# 16316339.net
KiCad netlist of a schematic drawn in EasyEDA Pro
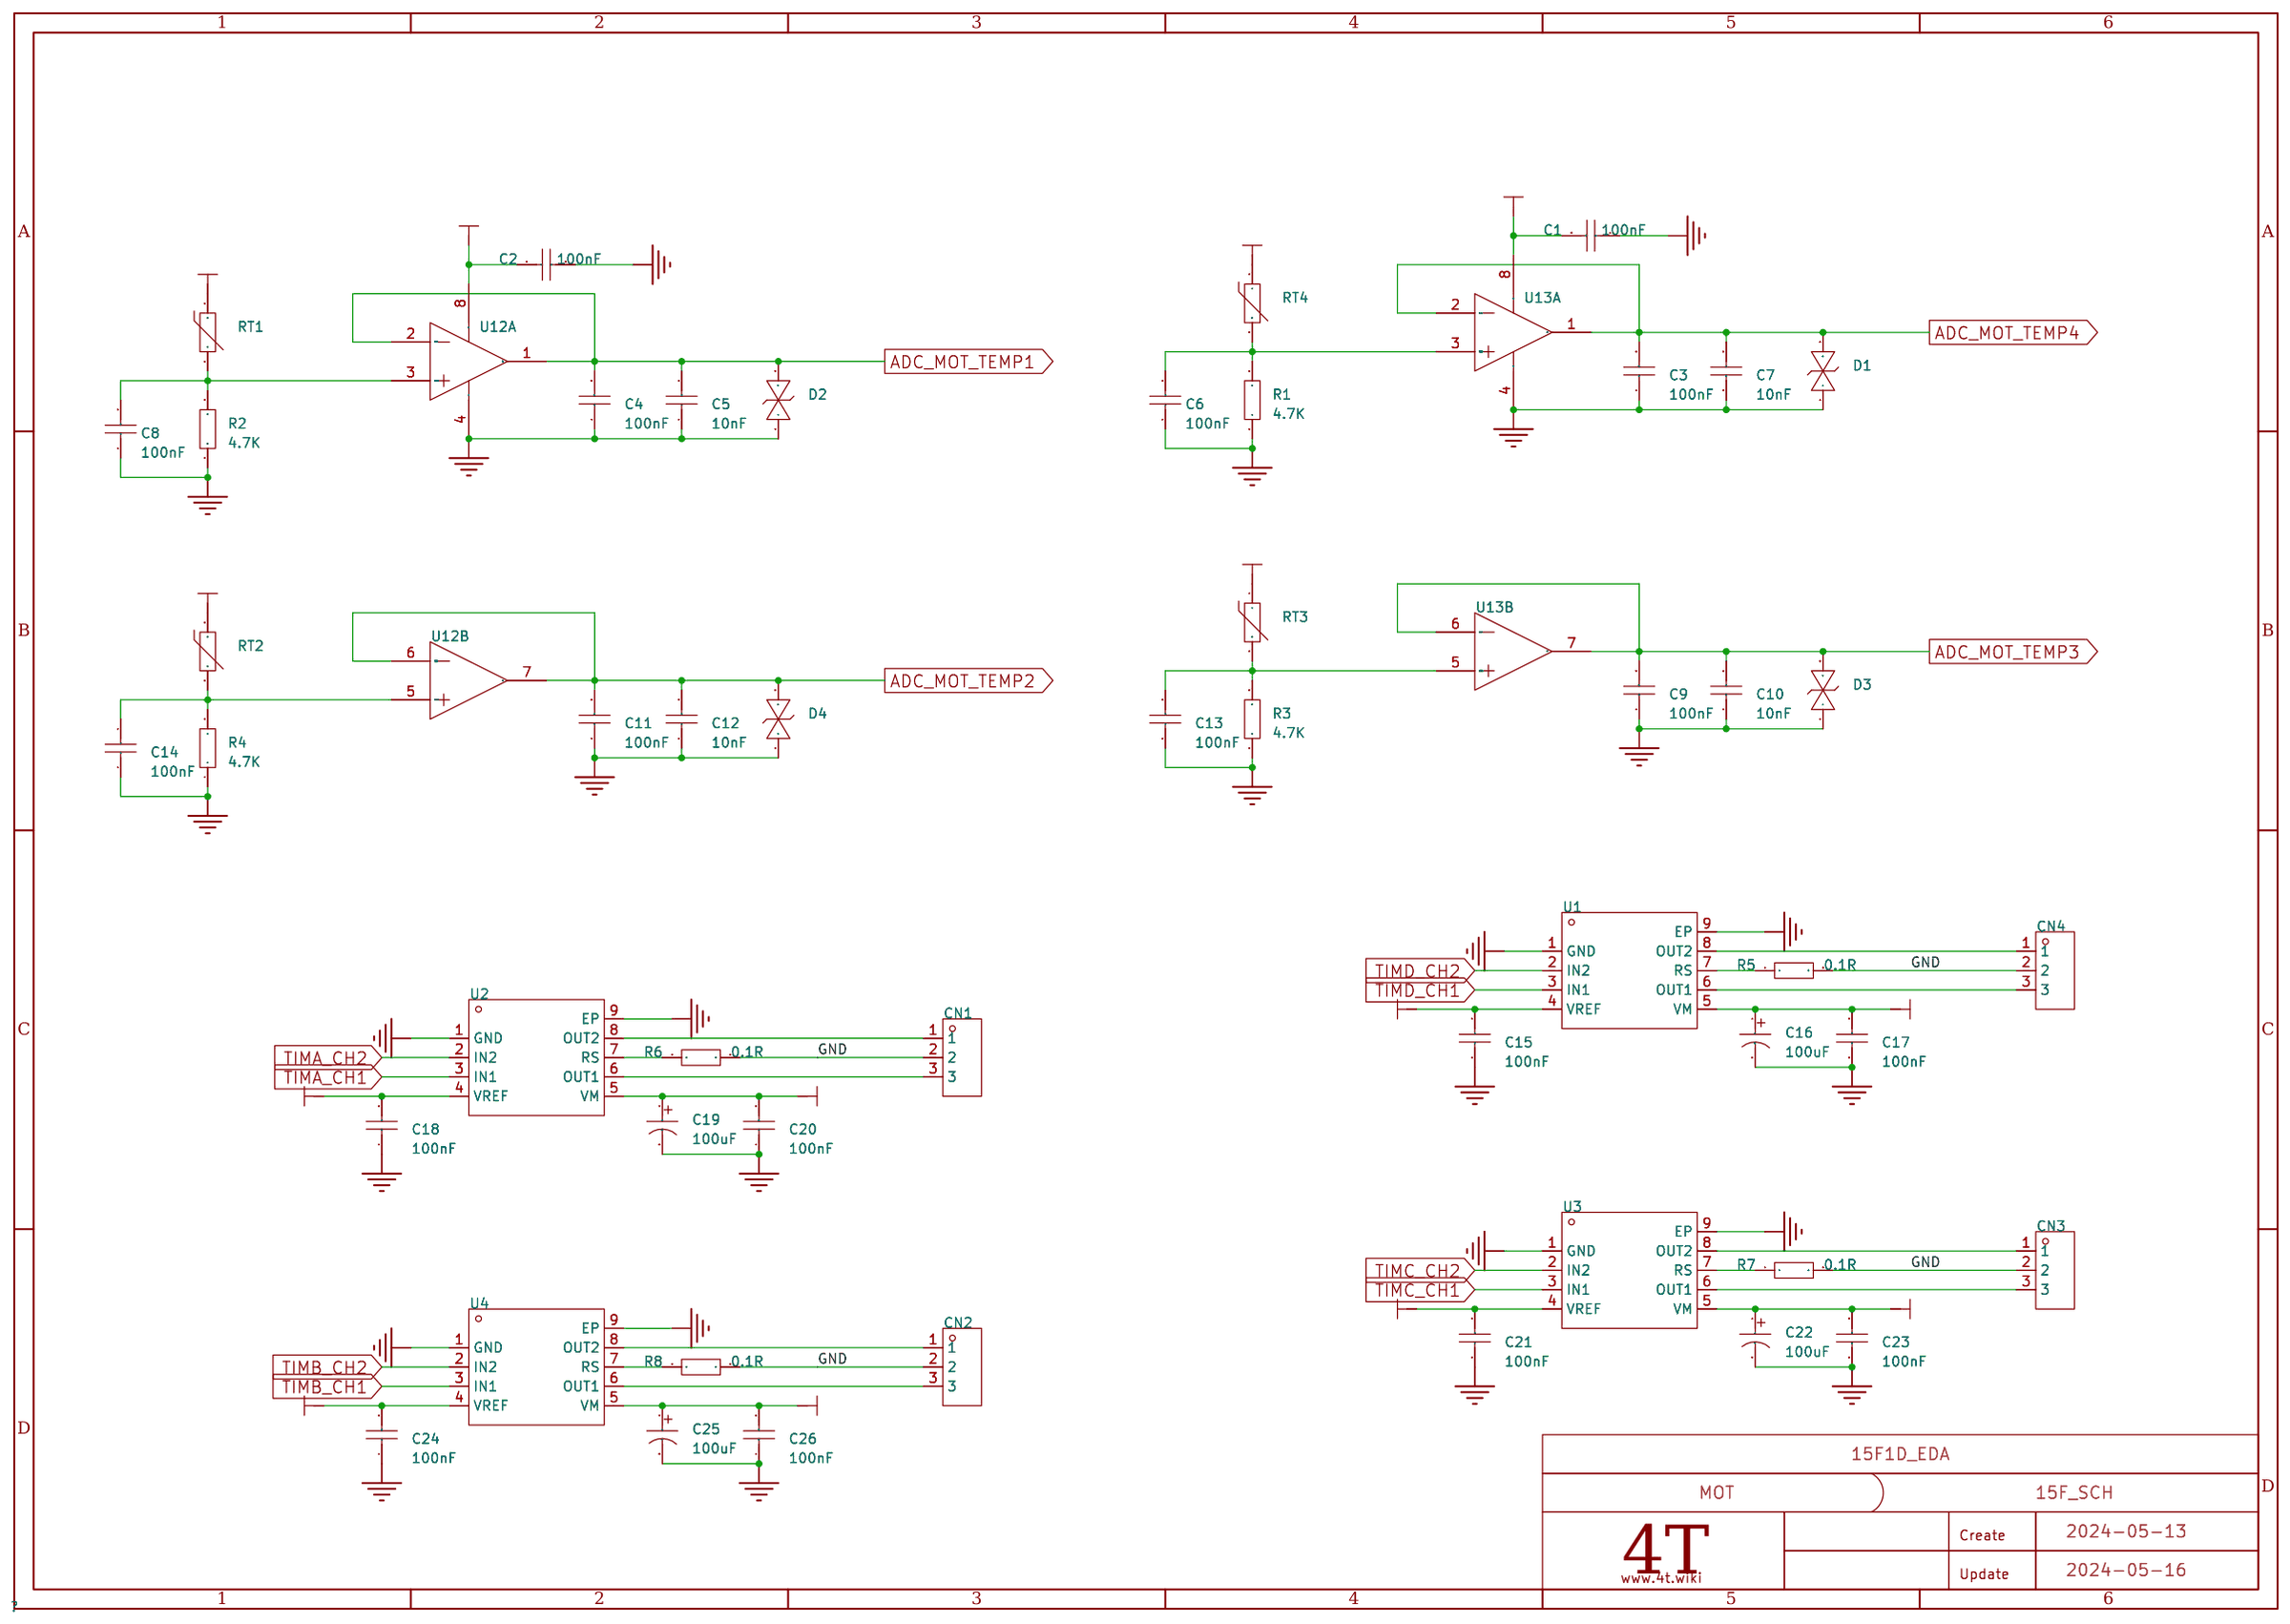
[diagram p0: MOT]
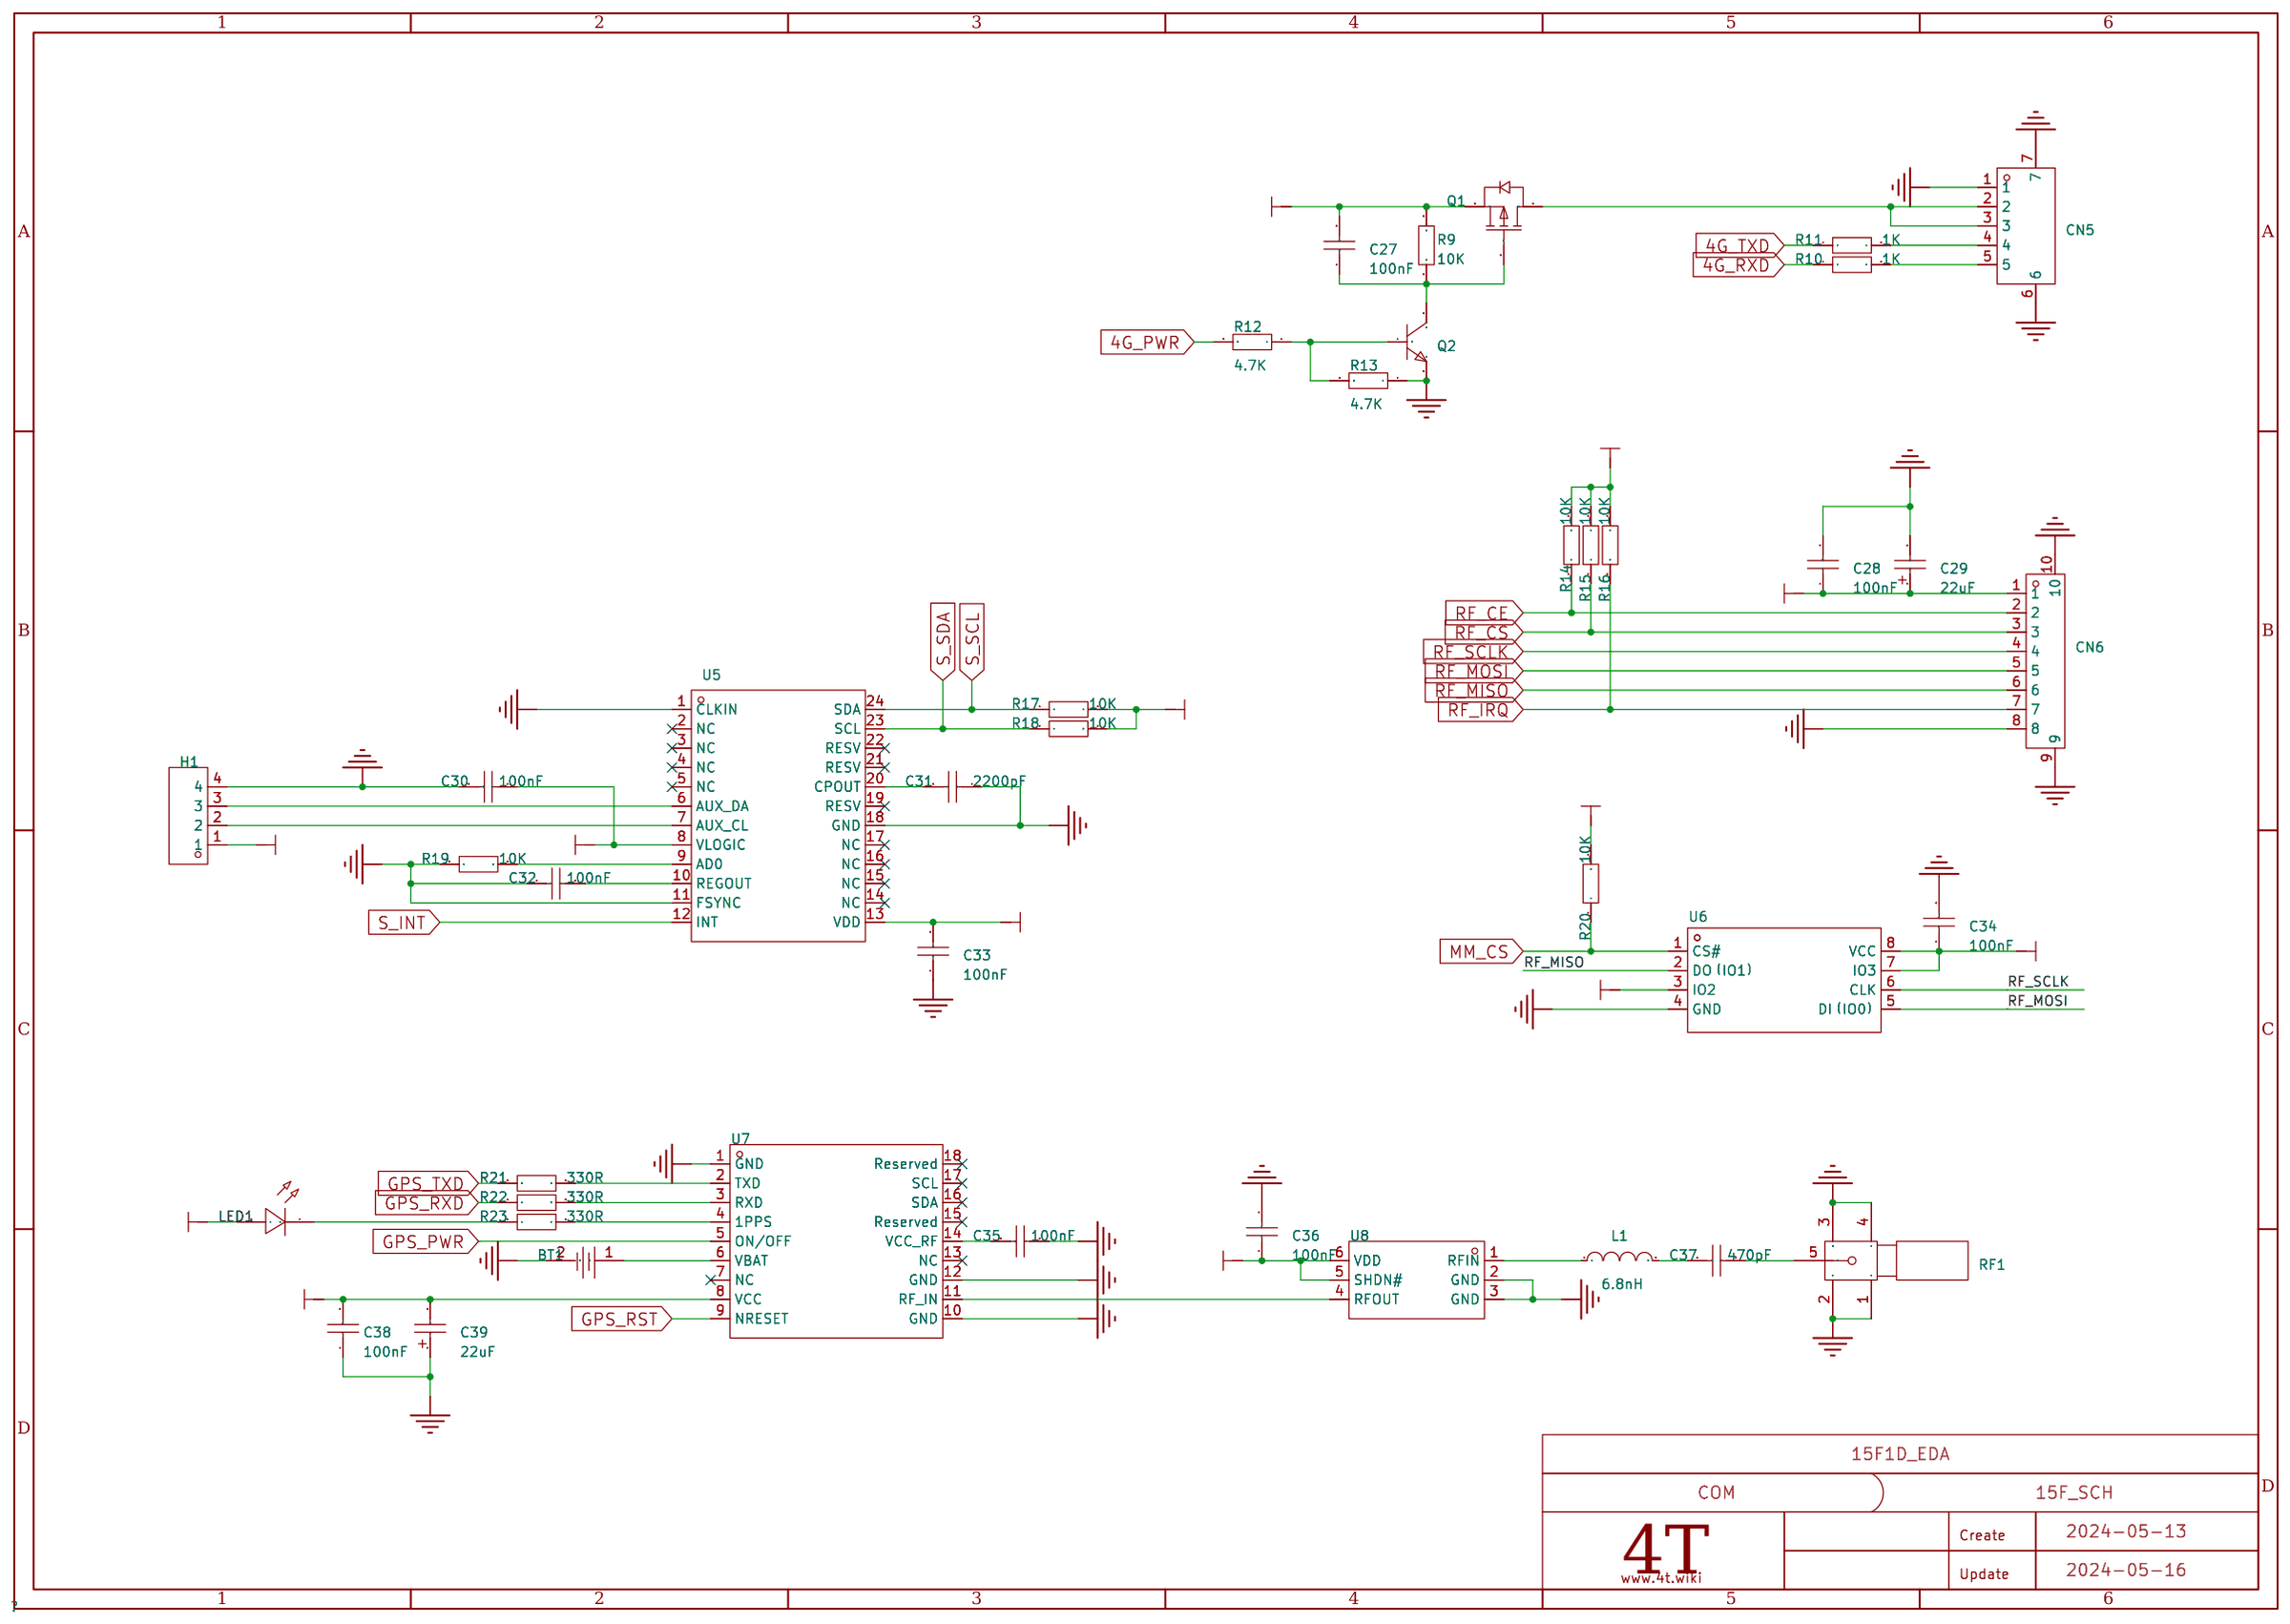
[diagram p1: COM]
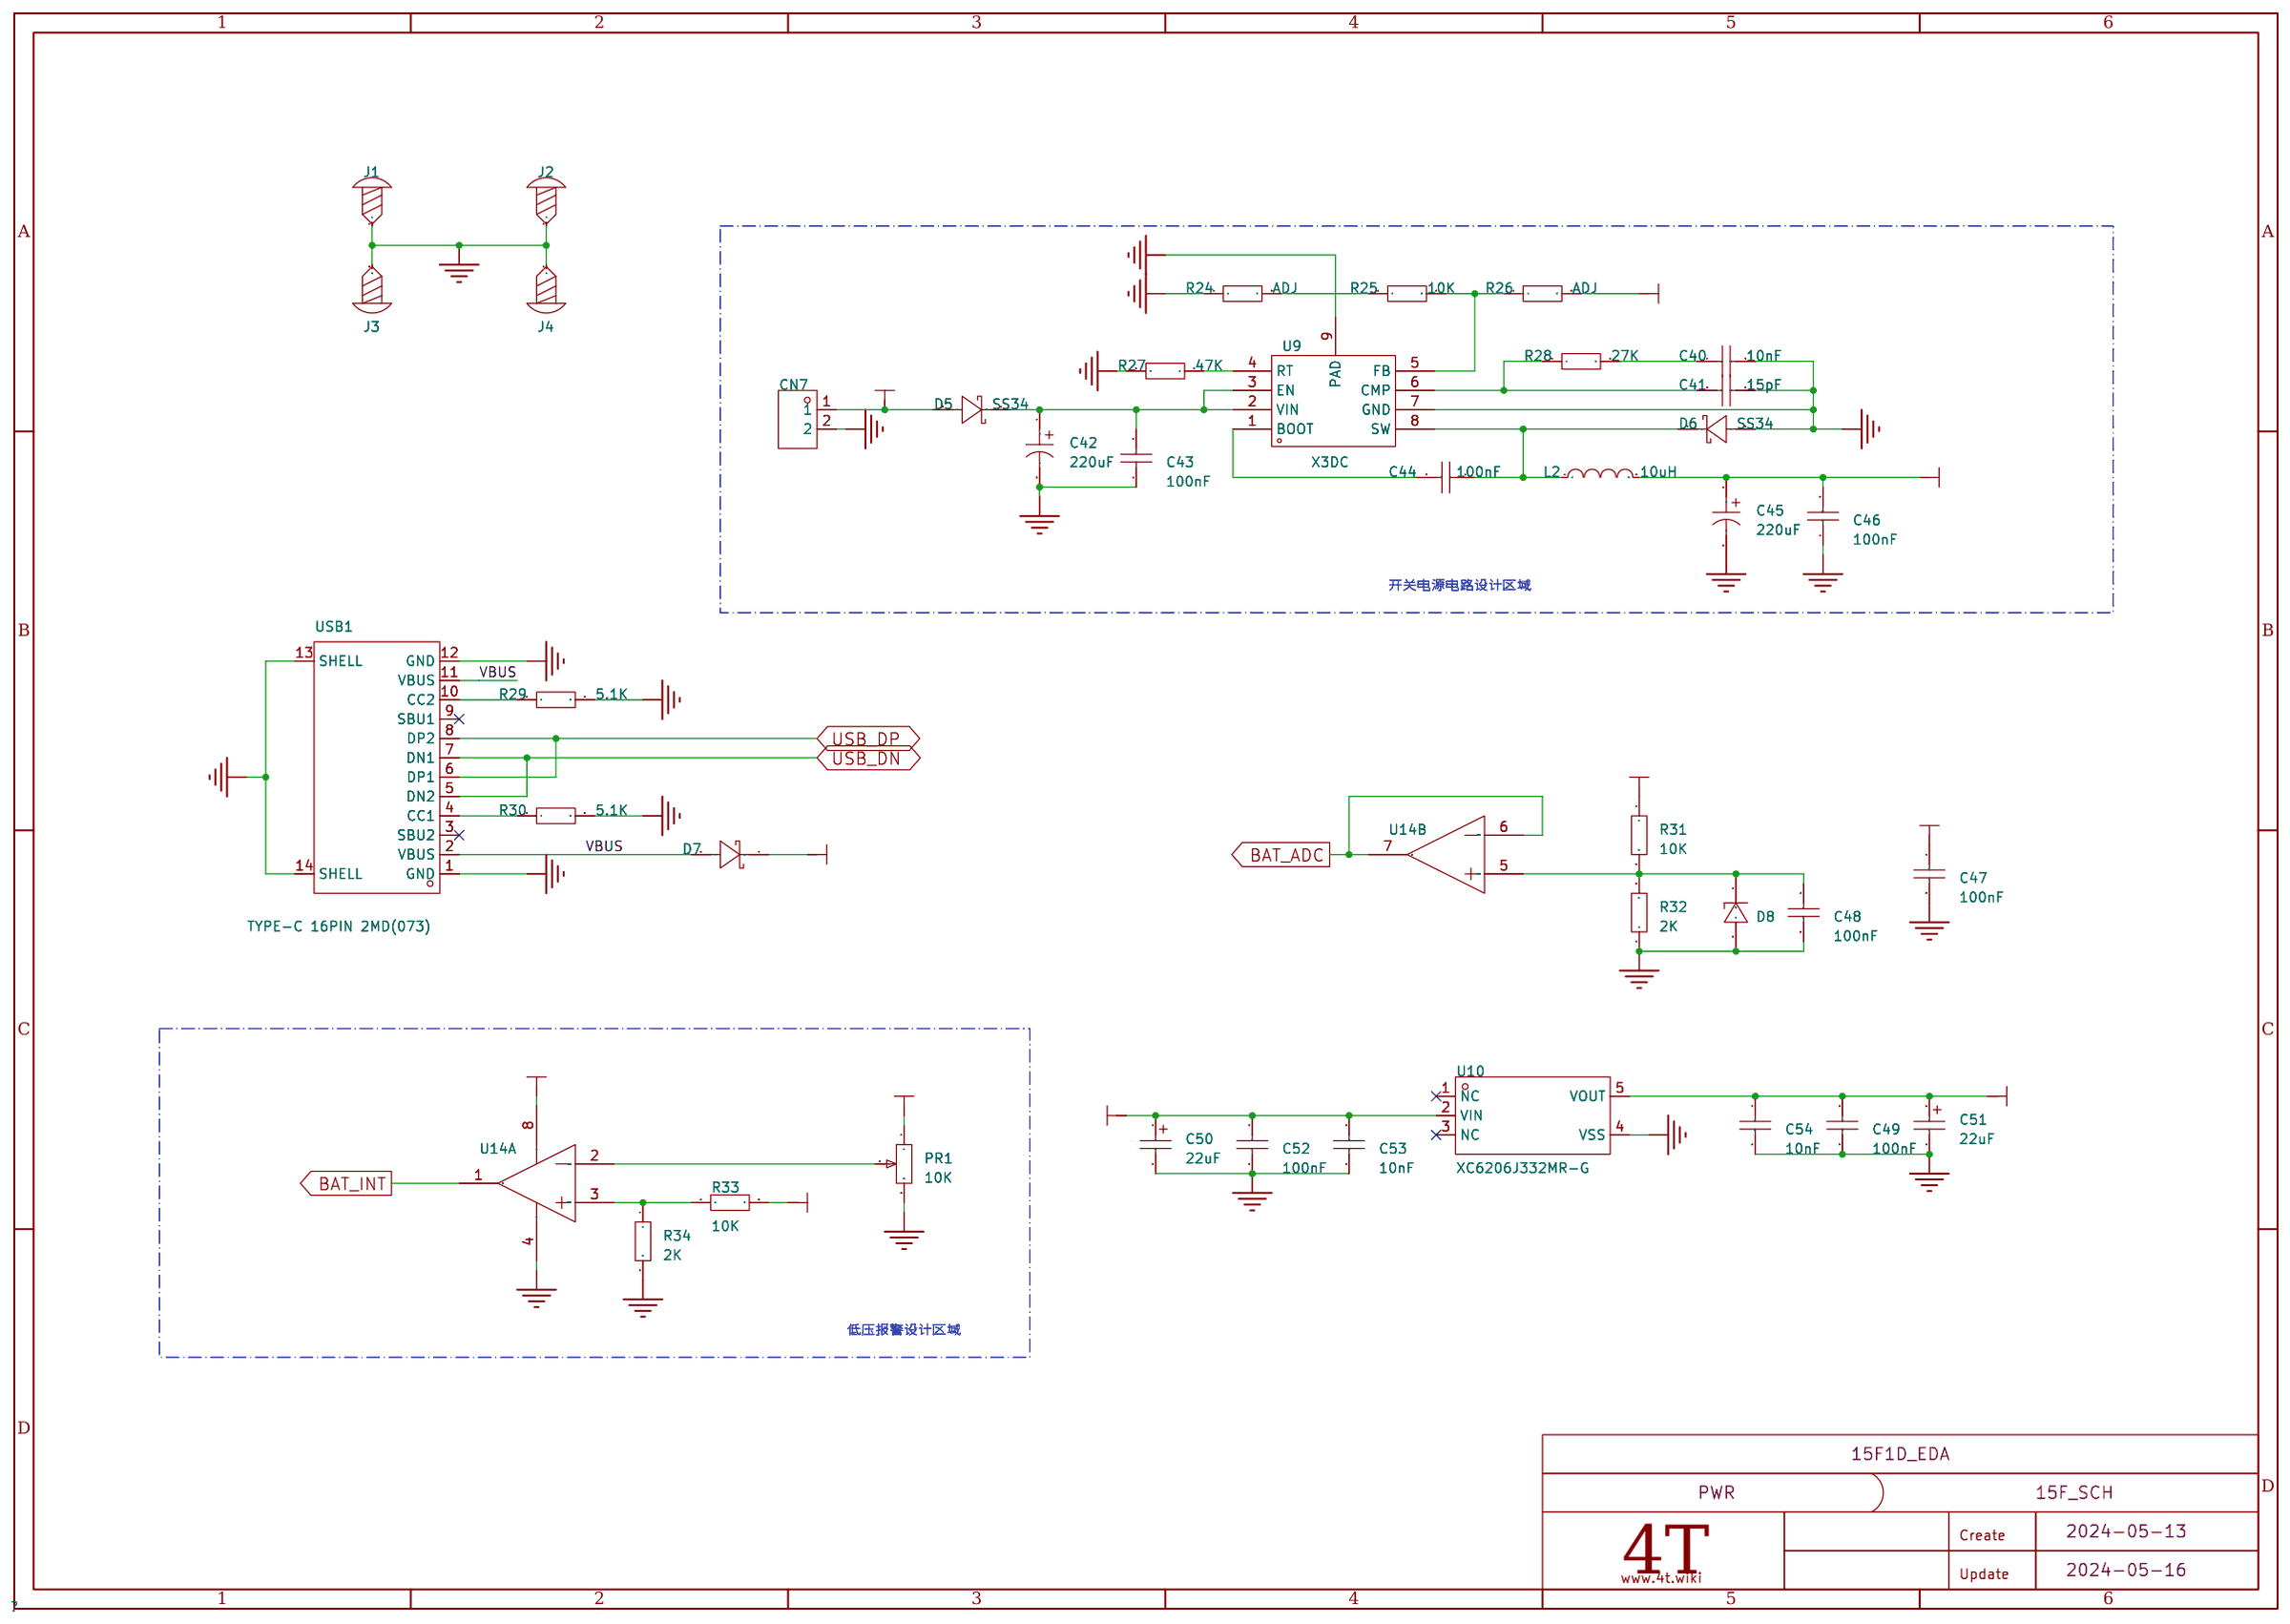
[diagram p2: PWR]
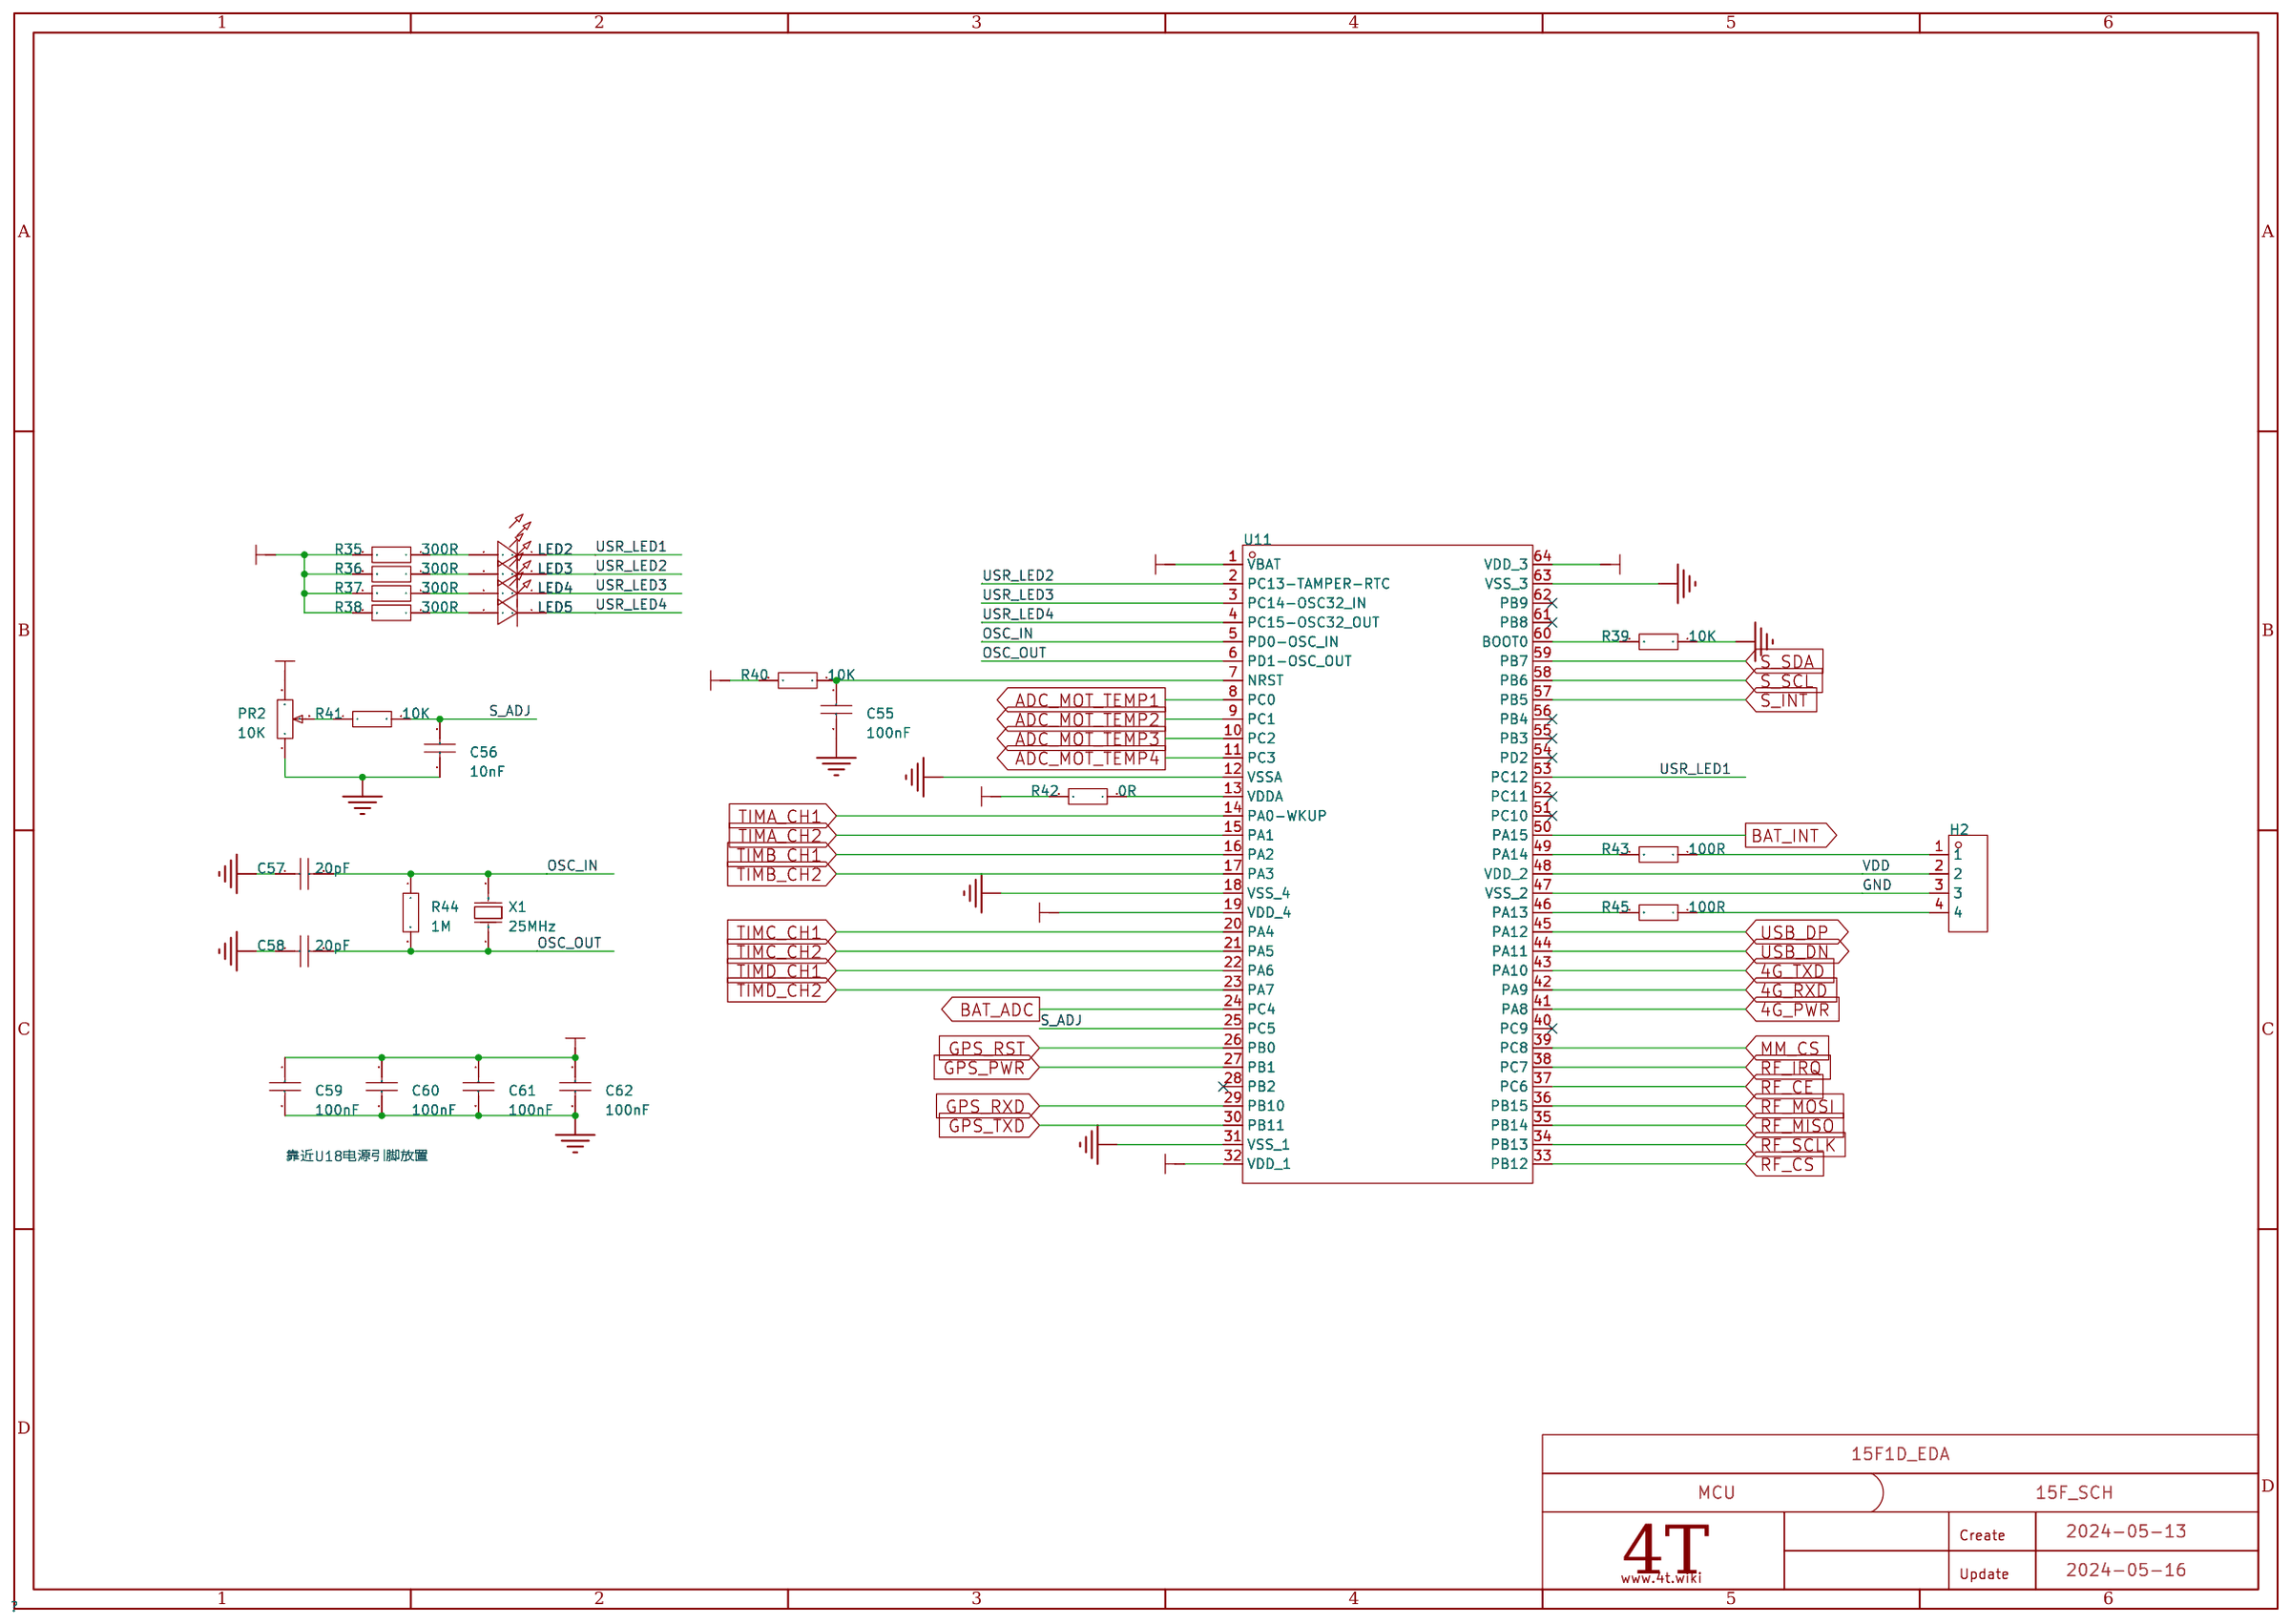
[diagram p3: MCU]

(export (version "E")
  (design (tool "Eeschema 10.0.6"))
  (components
    (comp (ref "C1")
      (value "100nF")
      (footprint "easyedapro:C0805")
      (description "容值:100nF;精度:±10%;额定电压:100V;材质(温度系数):X7R;")
      (fields
        (field (name "Manufacturer Part") "CC0805KKX7R0BB104")
        (field (name "Manufacturer") "YAGEO(国巨)")
      )
      (libsource (lib "easyedapro") (part "CC0805KKX7R0BB104"))
    )
    (comp (ref "C2")
      (value "100nF")
      (footprint "easyedapro:C0805")
      (description "容值:100nF;精度:±10%;额定电压:100V;材质(温度系数):X7R;")
      (fields
        (field (name "Manufacturer Part") "CC0805KKX7R0BB104")
        (field (name "Manufacturer") "YAGEO(国巨)")
      )
      (libsource (lib "easyedapro") (part "CC0805KKX7R0BB104"))
    )
    (comp (ref "C3")
      (value "100nF")
      (footprint "easyedapro:C0805")
      (description "容值:100nF;精度:±10%;额定电压:100V;材质(温度系数):X7R;")
      (fields
        (field (name "Manufacturer Part") "CC0805KKX7R0BB104")
        (field (name "Manufacturer") "YAGEO(国巨)")
      )
      (libsource (lib "easyedapro") (part "CC0805KKX7R0BB104"))
    )
    (comp (ref "C4")
      (value "100nF")
      (footprint "easyedapro:C0805")
      (description "容值:100nF;精度:±10%;额定电压:100V;材质(温度系数):X7R;")
      (fields
        (field (name "Manufacturer Part") "CC0805KKX7R0BB104")
        (field (name "Manufacturer") "YAGEO(国巨)")
      )
      (libsource (lib "easyedapro") (part "CC0805KKX7R0BB104"))
    )
    (comp (ref "C5")
      (value "10nF")
      (footprint "easyedapro:C0805")
      (description "容值:100nF;精度:±10%;额定电压:100V;材质(温度系数):X7R;")
      (fields
        (field (name "Manufacturer Part") "CC0805KKX7R0BB104")
        (field (name "Manufacturer") "YAGEO(国巨)")
      )
      (libsource (lib "easyedapro") (part "CC0805KKX7R0BB104"))
    )
    (comp (ref "C6")
      (value "100nF")
      (footprint "easyedapro:C0805")
      (description "容值:100nF;精度:±10%;额定电压:100V;材质(温度系数):X7R;")
      (fields
        (field (name "Manufacturer Part") "CC0805KKX7R0BB104")
        (field (name "Manufacturer") "YAGEO(国巨)")
      )
      (libsource (lib "easyedapro") (part "CC0805KKX7R0BB104"))
    )
    (comp (ref "C7")
      (value "10nF")
      (footprint "easyedapro:C0805")
      (description "容值:100nF;精度:±10%;额定电压:100V;材质(温度系数):X7R;")
      (fields
        (field (name "Manufacturer Part") "CC0805KKX7R0BB104")
        (field (name "Manufacturer") "YAGEO(国巨)")
      )
      (libsource (lib "easyedapro") (part "CC0805KKX7R0BB104"))
    )
    (comp (ref "C8")
      (value "100nF")
      (footprint "easyedapro:C0805")
      (description "容值:100nF;精度:±10%;额定电压:100V;材质(温度系数):X7R;")
      (fields
        (field (name "Manufacturer Part") "CC0805KKX7R0BB104")
        (field (name "Manufacturer") "YAGEO(国巨)")
      )
      (libsource (lib "easyedapro") (part "CC0805KKX7R0BB104"))
    )
    (comp (ref "C9")
      (value "100nF")
      (footprint "easyedapro:C0805")
      (description "容值:100nF;精度:±10%;额定电压:100V;材质(温度系数):X7R;")
      (fields
        (field (name "Manufacturer Part") "CC0805KKX7R0BB104")
        (field (name "Manufacturer") "YAGEO(国巨)")
      )
      (libsource (lib "easyedapro") (part "CC0805KKX7R0BB104"))
    )
    (comp (ref "C10")
      (value "10nF")
      (footprint "easyedapro:C0805")
      (description "容值:100nF;精度:±10%;额定电压:100V;材质(温度系数):X7R;")
      (fields
        (field (name "Manufacturer Part") "CC0805KKX7R0BB104")
        (field (name "Manufacturer") "YAGEO(国巨)")
      )
      (libsource (lib "easyedapro") (part "CC0805KKX7R0BB104"))
    )
    (comp (ref "C11")
      (value "100nF")
      (footprint "easyedapro:C0805")
      (description "容值:100nF;精度:±10%;额定电压:100V;材质(温度系数):X7R;")
      (fields
        (field (name "Manufacturer Part") "CC0805KKX7R0BB104")
        (field (name "Manufacturer") "YAGEO(国巨)")
      )
      (libsource (lib "easyedapro") (part "CC0805KKX7R0BB104"))
    )
    (comp (ref "C12")
      (value "10nF")
      (footprint "easyedapro:C0805")
      (description "容值:100nF;精度:±10%;额定电压:100V;材质(温度系数):X7R;")
      (fields
        (field (name "Manufacturer Part") "CC0805KKX7R0BB104")
        (field (name "Manufacturer") "YAGEO(国巨)")
      )
      (libsource (lib "easyedapro") (part "CC0805KKX7R0BB104"))
    )
    (comp (ref "C13")
      (value "100nF")
      (footprint "easyedapro:C0805")
      (description "容值:100nF;精度:±10%;额定电压:100V;材质(温度系数):X7R;")
      (fields
        (field (name "Manufacturer Part") "CC0805KKX7R0BB104")
        (field (name "Manufacturer") "YAGEO(国巨)")
      )
      (libsource (lib "easyedapro") (part "CC0805KKX7R0BB104"))
    )
    (comp (ref "C14")
      (value "100nF")
      (footprint "easyedapro:C0805")
      (description "容值:100nF;精度:±10%;额定电压:100V;材质(温度系数):X7R;")
      (fields
        (field (name "Manufacturer Part") "CC0805KKX7R0BB104")
        (field (name "Manufacturer") "YAGEO(国巨)")
      )
      (libsource (lib "easyedapro") (part "CC0805KKX7R0BB104"))
    )
    (comp (ref "C15")
      (value "100nF")
      (footprint "easyedapro:C0805")
      (description "容值:100nF;精度:±10%;额定电压:100V;材质(温度系数):X7R;")
      (fields
        (field (name "Manufacturer Part") "CC0805KKX7R0BB104")
        (field (name "Manufacturer") "YAGEO(国巨)")
      )
      (libsource (lib "easyedapro") (part "CC0805KKX7R0BB104"))
    )
    (comp (ref "C16")
      (value "100uF")
      (footprint "easyedapro:CAP-SMD_BD6.3-L6.6-W6.6-LS7.2-FD")
      (description "容值:100uF;精度:±20%;额定电压:16V;纹波电流:-;等效串联电阻:-;")
      (fields (field (name "Manufacturer Part") "RVT1C101M0605") (field (name "Manufacturer") "HONOR(荣誉)"))
      (libsource (lib "easyedapro") (part "RVT1C101M0605"))
    )
    (comp (ref "C17")
      (value "100nF")
      (footprint "easyedapro:C0805")
      (description "容值:100nF;精度:±10%;额定电压:100V;材质(温度系数):X7R;")
      (fields
        (field (name "Manufacturer Part") "CC0805KKX7R0BB104")
        (field (name "Manufacturer") "YAGEO(国巨)")
      )
      (libsource (lib "easyedapro") (part "CC0805KKX7R0BB104"))
    )
    (comp (ref "C18")
      (value "100nF")
      (footprint "easyedapro:C0805")
      (description "容值:100nF;精度:±10%;额定电压:100V;材质(温度系数):X7R;")
      (fields
        (field (name "Manufacturer Part") "CC0805KKX7R0BB104")
        (field (name "Manufacturer") "YAGEO(国巨)")
      )
      (libsource (lib "easyedapro") (part "CC0805KKX7R0BB104"))
    )
    (comp (ref "C19")
      (value "100uF")
      (footprint "easyedapro:CAP-SMD_BD6.3-L6.6-W6.6-LS7.2-FD")
      (description "容值:100uF;精度:±20%;额定电压:16V;纹波电流:-;等效串联电阻:-;")
      (fields (field (name "Manufacturer Part") "RVT1C101M0605") (field (name "Manufacturer") "HONOR(荣誉)"))
      (libsource (lib "easyedapro") (part "RVT1C101M0605"))
    )
    (comp (ref "C20")
      (value "100nF")
      (footprint "easyedapro:C0805")
      (description "容值:100nF;精度:±10%;额定电压:100V;材质(温度系数):X7R;")
      (fields
        (field (name "Manufacturer Part") "CC0805KKX7R0BB104")
        (field (name "Manufacturer") "YAGEO(国巨)")
      )
      (libsource (lib "easyedapro") (part "CC0805KKX7R0BB104"))
    )
    (comp (ref "C21")
      (value "100nF")
      (footprint "easyedapro:C0805")
      (description "容值:100nF;精度:±10%;额定电压:100V;材质(温度系数):X7R;")
      (fields
        (field (name "Manufacturer Part") "CC0805KKX7R0BB104")
        (field (name "Manufacturer") "YAGEO(国巨)")
      )
      (libsource (lib "easyedapro") (part "CC0805KKX7R0BB104"))
    )
    (comp (ref "C22")
      (value "100uF")
      (footprint "easyedapro:CAP-SMD_BD6.3-L6.6-W6.6-LS7.2-FD")
      (description "容值:100uF;精度:±20%;额定电压:16V;纹波电流:-;等效串联电阻:-;")
      (fields (field (name "Manufacturer Part") "RVT1C101M0605") (field (name "Manufacturer") "HONOR(荣誉)"))
      (libsource (lib "easyedapro") (part "RVT1C101M0605"))
    )
    (comp (ref "C23")
      (value "100nF")
      (footprint "easyedapro:C0805")
      (description "容值:100nF;精度:±10%;额定电压:100V;材质(温度系数):X7R;")
      (fields
        (field (name "Manufacturer Part") "CC0805KKX7R0BB104")
        (field (name "Manufacturer") "YAGEO(国巨)")
      )
      (libsource (lib "easyedapro") (part "CC0805KKX7R0BB104"))
    )
    (comp (ref "C24")
      (value "100nF")
      (footprint "easyedapro:C0805")
      (description "容值:100nF;精度:±10%;额定电压:100V;材质(温度系数):X7R;")
      (fields
        (field (name "Manufacturer Part") "CC0805KKX7R0BB104")
        (field (name "Manufacturer") "YAGEO(国巨)")
      )
      (libsource (lib "easyedapro") (part "CC0805KKX7R0BB104"))
    )
    (comp (ref "C25")
      (value "100uF")
      (footprint "easyedapro:CAP-SMD_BD6.3-L6.6-W6.6-LS7.2-FD")
      (description "容值:100uF;精度:±20%;额定电压:16V;纹波电流:-;等效串联电阻:-;")
      (fields (field (name "Manufacturer Part") "RVT1C101M0605") (field (name "Manufacturer") "HONOR(荣誉)"))
      (libsource (lib "easyedapro") (part "RVT1C101M0605"))
    )
    (comp (ref "C26")
      (value "100nF")
      (footprint "easyedapro:C0805")
      (description "容值:100nF;精度:±10%;额定电压:100V;材质(温度系数):X7R;")
      (fields
        (field (name "Manufacturer Part") "CC0805KKX7R0BB104")
        (field (name "Manufacturer") "YAGEO(国巨)")
      )
      (libsource (lib "easyedapro") (part "CC0805KKX7R0BB104"))
    )
    (comp (ref "CN1")
      (value "2.54-1*3P")
      (footprint "easyedapro:CONN-TH_C722693")
      (description "插针结构:1x3P;间距:2.5mm;安装方式:直插;参考系列:-;总PIN数:3P;排数:1;每排PIN数:3;行距:-;额定电流:2A;工作温度范围:-25°C~+85°C;")
      (fields (field (name "Manufacturer") "CAX(创都)"))
      (libsource (lib "easyedapro") (part "2.54-1*3P"))
    )
    (comp (ref "CN2")
      (value "2.54-1*3P")
      (footprint "easyedapro:CONN-TH_C722693")
      (description "插针结构:1x3P;间距:2.5mm;安装方式:直插;参考系列:-;总PIN数:3P;排数:1;每排PIN数:3;行距:-;额定电流:2A;工作温度范围:-25°C~+85°C;")
      (fields (field (name "Manufacturer") "CAX(创都)"))
      (libsource (lib "easyedapro") (part "2.54-1*3P"))
    )
    (comp (ref "CN3")
      (value "2.54-1*3P")
      (footprint "easyedapro:CONN-TH_C722693")
      (description "插针结构:1x3P;间距:2.5mm;安装方式:直插;参考系列:-;总PIN数:3P;排数:1;每排PIN数:3;行距:-;额定电流:2A;工作温度范围:-25°C~+85°C;")
      (fields (field (name "Manufacturer") "CAX(创都)"))
      (libsource (lib "easyedapro") (part "2.54-1*3P"))
    )
    (comp (ref "CN4")
      (value "2.54-1*3P")
      (footprint "easyedapro:CONN-TH_C722693")
      (description "插针结构:1x3P;间距:2.5mm;安装方式:直插;参考系列:-;总PIN数:3P;排数:1;每排PIN数:3;行距:-;额定电流:2A;工作温度范围:-25°C~+85°C;")
      (fields (field (name "Manufacturer") "CAX(创都)"))
      (libsource (lib "easyedapro") (part "2.54-1*3P"))
    )
    (comp (ref "D1")
      (value "H3V3LD5B")
      (footprint "easyedapro:SOD-523F_L1.7-W0.9-LS1.7-BI")
      (description "极性:双向;反向截止电压(Vrwm):3.3V;最大钳位电压:12V;峰值脉冲电流(Ipp)@10/1000us:8A;峰值脉冲功率(Ppp)@10/1000us:100W;击穿电压:6.5V;")
      (fields (field (name "Manufacturer") "宏迦橙"))
      (libsource (lib "easyedapro") (part "H3V3LD5B"))
    )
    (comp (ref "D2")
      (value "H3V3LD5B")
      (footprint "easyedapro:SOD-523F_L1.7-W0.9-LS1.7-BI")
      (description "极性:双向;反向截止电压(Vrwm):3.3V;最大钳位电压:12V;峰值脉冲电流(Ipp)@10/1000us:8A;峰值脉冲功率(Ppp)@10/1000us:100W;击穿电压:6.5V;")
      (fields (field (name "Manufacturer") "宏迦橙"))
      (libsource (lib "easyedapro") (part "H3V3LD5B"))
    )
    (comp (ref "D3")
      (value "H3V3LD5B")
      (footprint "easyedapro:SOD-523F_L1.7-W0.9-LS1.7-BI")
      (description "极性:双向;反向截止电压(Vrwm):3.3V;最大钳位电压:12V;峰值脉冲电流(Ipp)@10/1000us:8A;峰值脉冲功率(Ppp)@10/1000us:100W;击穿电压:6.5V;")
      (fields (field (name "Manufacturer") "宏迦橙"))
      (libsource (lib "easyedapro") (part "H3V3LD5B"))
    )
    (comp (ref "D4")
      (value "H3V3LD5B")
      (footprint "easyedapro:SOD-523F_L1.7-W0.9-LS1.7-BI")
      (description "极性:双向;反向截止电压(Vrwm):3.3V;最大钳位电压:12V;峰值脉冲电流(Ipp)@10/1000us:8A;峰值脉冲功率(Ppp)@10/1000us:100W;击穿电压:6.5V;")
      (fields (field (name "Manufacturer") "宏迦橙"))
      (libsource (lib "easyedapro") (part "H3V3LD5B"))
    )
    (comp (ref "R1") (value "4.7K") (footprint "easyedapro:R0805") (libsource (lib "easyedapro") (part "电阻")))
    (comp (ref "R2") (value "4.7K") (footprint "easyedapro:R0805") (libsource (lib "easyedapro") (part "电阻")))
    (comp (ref "R3") (value "4.7K") (footprint "easyedapro:R0805") (libsource (lib "easyedapro") (part "电阻")))
    (comp (ref "R4") (value "4.7K") (footprint "easyedapro:R0805") (libsource (lib "easyedapro") (part "电阻")))
    (comp (ref "R5") (value "0.1R") (footprint "easyedapro:R0805") (libsource (lib "easyedapro") (part "电阻")))
    (comp (ref "R6") (value "0.1R") (footprint "easyedapro:R0805") (libsource (lib "easyedapro") (part "电阻")))
    (comp (ref "R7") (value "0.1R") (footprint "easyedapro:R0805") (libsource (lib "easyedapro") (part "电阻")))
    (comp (ref "R8") (value "0.1R") (footprint "easyedapro:R0805") (libsource (lib "easyedapro") (part "电阻")))
    (comp (ref "RT1")
      (value "NTC 5D-7")
      (footprint "easyedapro:RES-TH_L8.5-W5.5-P5.00-D0.6-S5.50")
      (description "阻值(25°C):5Ω;B值(25°C/50°C):-;电阻精度:-;功率:-;B值精度:-;最大稳态电流(25°C):2A;")
      (fields (field (name "Manufacturer") "RUILON(瑞隆源)"))
      (libsource (lib "easyedapro") (part "NTC 5D-7"))
    )
    (comp (ref "RT2")
      (value "NTC 5D-7")
      (footprint "easyedapro:RES-TH_L8.5-W5.5-P5.00-D0.6-S5.50")
      (description "阻值(25°C):5Ω;B值(25°C/50°C):-;电阻精度:-;功率:-;B值精度:-;最大稳态电流(25°C):2A;")
      (fields (field (name "Manufacturer") "RUILON(瑞隆源)"))
      (libsource (lib "easyedapro") (part "NTC 5D-7"))
    )
    (comp (ref "RT3")
      (value "NTC 5D-7")
      (footprint "easyedapro:RES-TH_L8.5-W5.5-P5.00-D0.6-S5.50")
      (description "阻值(25°C):5Ω;B值(25°C/50°C):-;电阻精度:-;功率:-;B值精度:-;最大稳态电流(25°C):2A;")
      (fields (field (name "Manufacturer") "RUILON(瑞隆源)"))
      (libsource (lib "easyedapro") (part "NTC 5D-7"))
    )
    (comp (ref "RT4")
      (value "NTC 5D-7")
      (footprint "easyedapro:RES-TH_L8.5-W5.5-P5.00-D0.6-S5.50")
      (description "阻值(25°C):5Ω;B值(25°C/50°C):-;电阻精度:-;功率:-;B值精度:-;最大稳态电流(25°C):2A;")
      (fields (field (name "Manufacturer") "RUILON(瑞隆源)"))
      (libsource (lib "easyedapro") (part "NTC 5D-7"))
    )
    (comp (ref "U1")
      (value "TB67H450FNG,EL")
      (footprint "easyedapro:HSOP-8_L5.0-W4.0-P1.27-LS6.2-BL-EP")
      (description "驱动电机类型:有刷直流电机;输出电流:3.5A;")
      (fields (field (name "Manufacturer") "TOSHIBA(东芝)"))
      (libsource (lib "easyedapro") (part "TB67H450FNG,EL"))
    )
    (comp (ref "U2")
      (value "TB67H450FNG,EL")
      (footprint "easyedapro:HSOP-8_L5.0-W4.0-P1.27-LS6.2-BL-EP")
      (description "驱动电机类型:有刷直流电机;输出电流:3.5A;")
      (fields (field (name "Manufacturer") "TOSHIBA(东芝)"))
      (libsource (lib "easyedapro") (part "TB67H450FNG,EL"))
    )
    (comp (ref "U3")
      (value "TB67H450FNG,EL")
      (footprint "easyedapro:HSOP-8_L5.0-W4.0-P1.27-LS6.2-BL-EP")
      (description "驱动电机类型:有刷直流电机;输出电流:3.5A;")
      (fields (field (name "Manufacturer") "TOSHIBA(东芝)"))
      (libsource (lib "easyedapro") (part "TB67H450FNG,EL"))
    )
    (comp (ref "U4")
      (value "TB67H450FNG,EL")
      (footprint "easyedapro:HSOP-8_L5.0-W4.0-P1.27-LS6.2-BL-EP")
      (description "驱动电机类型:有刷直流电机;输出电流:3.5A;")
      (fields (field (name "Manufacturer") "TOSHIBA(东芝)"))
      (libsource (lib "easyedapro") (part "TB67H450FNG,EL"))
    )
    (comp (ref "U12")
      (value "GS8552-SR")
      (footprint "easyedapro:SOIC-8_L4.9-W3.9-P1.27-LS6.0-BL")
      (description "放大器数:双路;增益带宽积(GBP):1.8MHz;压摆率(SR):0.95V/us;")
      (fields (field (name "Manufacturer") "Gainsil(聚洵)"))
      (libsource (lib "easyedapro") (part "GS8552-SR"))
    )
    (comp (ref "U13")
      (value "GS8552-SR")
      (footprint "easyedapro:SOIC-8_L4.9-W3.9-P1.27-LS6.0-BL")
      (description "放大器数:双路;增益带宽积(GBP):1.8MHz;压摆率(SR):0.95V/us;")
      (fields (field (name "Manufacturer") "Gainsil(聚洵)"))
      (libsource (lib "easyedapro") (part "GS8552-SR"))
    )
    (comp (ref "BT1")
      (value "CR1220-A")
      (footprint "easyedapro:BAT-SMD_CR1220-2")
      (libsource (lib "easyedapro") (part "CR1220-A"))
    )
    (comp (ref "C27")
      (value "100nF")
      (footprint "easyedapro:C0805")
      (description "容值:100nF;精度:±10%;额定电压:100V;材质(温度系数):X7R;")
      (fields
        (field (name "Manufacturer Part") "CC0805KKX7R0BB104")
        (field (name "Manufacturer") "YAGEO(国巨)")
      )
      (libsource (lib "easyedapro") (part "CC0805KKX7R0BB104"))
    )
    (comp (ref "C28")
      (value "100nF")
      (footprint "easyedapro:C0805")
      (description "容值:100nF;精度:±10%;额定电压:100V;材质(温度系数):X7R;")
      (fields
        (field (name "Manufacturer Part") "CC0805KKX7R0BB104")
        (field (name "Manufacturer") "YAGEO(国巨)")
      )
      (libsource (lib "easyedapro") (part "CC0805KKX7R0BB104"))
    )
    (comp (ref "C29")
      (value "22uF")
      (footprint "easyedapro:CASE-A_3216")
      (description "容值:22uF;精度:±10%;额定电压:10V;等效串联电阻:3Ω@100kHz;")
      (fields (field (name "Manufacturer Part") "TAJA226K010RNJ") (field (name "Manufacturer") "Kyocera AVX"))
      (libsource (lib "easyedapro") (part "TAJA226K010RNJ"))
    )
    (comp (ref "C30")
      (value "100nF")
      (footprint "easyedapro:C0805")
      (description "容值:100nF;精度:±10%;额定电压:100V;材质(温度系数):X7R;")
      (fields
        (field (name "Manufacturer Part") "CC0805KKX7R0BB104")
        (field (name "Manufacturer") "YAGEO(国巨)")
      )
      (libsource (lib "easyedapro") (part "CC0805KKX7R0BB104"))
    )
    (comp (ref "C31")
      (value "2200pF")
      (footprint "easyedapro:C0805")
      (description "容值:100nF;精度:±10%;额定电压:100V;材质(温度系数):X7R;")
      (fields
        (field (name "Manufacturer Part") "CC0805KKX7R0BB104")
        (field (name "Manufacturer") "YAGEO(国巨)")
      )
      (libsource (lib "easyedapro") (part "CC0805KKX7R0BB104"))
    )
    (comp (ref "C32")
      (value "100nF")
      (footprint "easyedapro:C0805")
      (description "容值:100nF;精度:±10%;额定电压:100V;材质(温度系数):X7R;")
      (fields
        (field (name "Manufacturer Part") "CC0805KKX7R0BB104")
        (field (name "Manufacturer") "YAGEO(国巨)")
      )
      (libsource (lib "easyedapro") (part "CC0805KKX7R0BB104"))
    )
    (comp (ref "C33")
      (value "100nF")
      (footprint "easyedapro:C0805")
      (description "容值:100nF;精度:±10%;额定电压:100V;材质(温度系数):X7R;")
      (fields
        (field (name "Manufacturer Part") "CC0805KKX7R0BB104")
        (field (name "Manufacturer") "YAGEO(国巨)")
      )
      (libsource (lib "easyedapro") (part "CC0805KKX7R0BB104"))
    )
    (comp (ref "C34")
      (value "100nF")
      (footprint "easyedapro:C0805")
      (description "容值:100nF;精度:±10%;额定电压:100V;材质(温度系数):X7R;")
      (fields
        (field (name "Manufacturer Part") "CC0805KKX7R0BB104")
        (field (name "Manufacturer") "YAGEO(国巨)")
      )
      (libsource (lib "easyedapro") (part "CC0805KKX7R0BB104"))
    )
    (comp (ref "C35")
      (value "100nF")
      (footprint "easyedapro:C0805")
      (description "容值:100nF;精度:±10%;额定电压:100V;材质(温度系数):X7R;")
      (fields
        (field (name "Manufacturer Part") "CC0805KKX7R0BB104")
        (field (name "Manufacturer") "YAGEO(国巨)")
      )
      (libsource (lib "easyedapro") (part "CC0805KKX7R0BB104"))
    )
    (comp (ref "C36")
      (value "100nF")
      (footprint "easyedapro:C0805")
      (description "容值:100nF;精度:±10%;额定电压:100V;材质(温度系数):X7R;")
      (fields
        (field (name "Manufacturer Part") "CC0805KKX7R0BB104")
        (field (name "Manufacturer") "YAGEO(国巨)")
      )
      (libsource (lib "easyedapro") (part "CC0805KKX7R0BB104"))
    )
    (comp (ref "C37")
      (value "470pF")
      (footprint "easyedapro:C0805")
      (description "容值:100nF;精度:±10%;额定电压:100V;材质(温度系数):X7R;")
      (fields
        (field (name "Manufacturer Part") "CC0805KKX7R0BB104")
        (field (name "Manufacturer") "YAGEO(国巨)")
      )
      (libsource (lib "easyedapro") (part "CC0805KKX7R0BB104"))
    )
    (comp (ref "C38")
      (value "100nF")
      (footprint "easyedapro:C0805")
      (description "容值:100nF;精度:±10%;额定电压:100V;材质(温度系数):X7R;")
      (fields
        (field (name "Manufacturer Part") "CC0805KKX7R0BB104")
        (field (name "Manufacturer") "YAGEO(国巨)")
      )
      (libsource (lib "easyedapro") (part "CC0805KKX7R0BB104"))
    )
    (comp (ref "C39")
      (value "22uF")
      (footprint "easyedapro:CASE-A_3216")
      (description "容值:22uF;精度:±10%;额定电压:10V;等效串联电阻:3Ω@100kHz;")
      (fields (field (name "Manufacturer Part") "TAJA226K010RNJ") (field (name "Manufacturer") "Kyocera AVX"))
      (libsource (lib "easyedapro") (part "TAJA226K010RNJ"))
    )
    (comp (ref "CN5")
      (value "ZX-XH2.54-5PWT")
      (footprint "easyedapro:CONN-SMD_5P-P2.54_MEGASTAR_ZX-XH2.54-5PWT")
      (fields (field (name "Manufacturer") "Megastar(兆星)"))
      (libsource (lib "easyedapro") (part "ZX-XH2.54-5PWT"))
    )
    (comp (ref "CN6")
      (value "2.54-8P WT")
      (footprint "easyedapro:CONN-SMD_8P-P2.50_2.54-8P-WT")
      (description "插针结构:1x8P;间距:2.54mm;安装方式:卧贴;参考系列:XH;总PIN数:8P;排数:1;每排PIN数:8;额定电流:3A;工作温度范围:-25°C~+85°C;")
      (fields (field (name "Manufacturer") "SHOU HAN(首韩)"))
      (libsource (lib "easyedapro") (part "2.54-8P WT"))
    )
    (comp (ref "H1")
      (value "~")
      (footprint "easyedapro:HDR-TH_4P-P2.54-V-F")
      (libsource (lib "easyedapro") (part "2.54-1*4P母"))
    )
    (comp (ref "L1")
      (value "6.8nH")
      (footprint "easyedapro:L0805")
      (description "电感值:6.8nH;精度:±5%;额定电流:600mA;饱和电流(Isat):-;直流电阻(DCR):110mΩ;")
      (fields
        (field (name "Manufacturer Part") "BKW0805UC6N8JGT")
        (field (name "Manufacturer") "FH-BK(风华邦科)")
      )
      (libsource (lib "easyedapro") (part "BKW0805UC6N8JGT"))
    )
    (comp (ref "LED1")
      (value "~")
      (footprint "easyedapro:LED_0805")
      (libsource (lib "easyedapro") (part "LED_G"))
    )
    (comp (ref "Q1")
      (value "AO3401A")
      (footprint "easyedapro:SOT-23_L2.9-W1.3-P1.90-LS2.4-BR")
      (fields (field (name "Manufacturer") "AOS"))
      (libsource (lib "easyedapro") (part "AO3401A"))
    )
    (comp (ref "Q2")
      (value "S8050 J3Y")
      (footprint "easyedapro:SOT-23-3_L3.0-W1.7-P0.95-LS2.9-BR")
      (description "晶体管类型:NPN;集电极电流(Ic):500mA;集射极击穿电压(Vceo):25V;功率(Pd):300mW;直流电流增益(hFE@Ic,Vce):200@50mA,1V;")
      (fields (field (name "Manufacturer") "CJ(江苏长电/长晶)"))
      (libsource (lib "easyedapro") (part "S8050_C2146"))
    )
    (comp (ref "R9") (value "10K") (footprint "easyedapro:R0805") (libsource (lib "easyedapro") (part "电阻")))
    (comp (ref "R10") (value "1K") (footprint "easyedapro:R0805") (libsource (lib "easyedapro") (part "电阻")))
    (comp (ref "R11") (value "1K") (footprint "easyedapro:R0805") (libsource (lib "easyedapro") (part "电阻")))
    (comp (ref "R12")
      (value "4.7K")
      (footprint "easyedapro:R0805")
      (libsource (lib "easyedapro") (part "电阻"))
    )
    (comp (ref "R13")
      (value "4.7K")
      (footprint "easyedapro:R0805")
      (libsource (lib "easyedapro") (part "电阻"))
    )
    (comp (ref "R14") (value "10K") (footprint "easyedapro:R0805") (libsource (lib "easyedapro") (part "电阻")))
    (comp (ref "R15") (value "10K") (footprint "easyedapro:R0805") (libsource (lib "easyedapro") (part "电阻")))
    (comp (ref "R16") (value "10K") (footprint "easyedapro:R0805") (libsource (lib "easyedapro") (part "电阻")))
    (comp (ref "R17") (value "10K") (footprint "easyedapro:R0805") (libsource (lib "easyedapro") (part "电阻")))
    (comp (ref "R18") (value "10K") (footprint "easyedapro:R0805") (libsource (lib "easyedapro") (part "电阻")))
    (comp (ref "R19") (value "10K") (footprint "easyedapro:R0805") (libsource (lib "easyedapro") (part "电阻")))
    (comp (ref "R20") (value "10K") (footprint "easyedapro:R0805") (libsource (lib "easyedapro") (part "电阻")))
    (comp (ref "R21")
      (value "330R")
      (footprint "easyedapro:R0805")
      (libsource (lib "easyedapro") (part "电阻"))
    )
    (comp (ref "R22")
      (value "330R")
      (footprint "easyedapro:R0805")
      (libsource (lib "easyedapro") (part "电阻"))
    )
    (comp (ref "R23")
      (value "330R")
      (footprint "easyedapro:R0805")
      (libsource (lib "easyedapro") (part "电阻"))
    )
    (comp (ref "RF1")
      (value "BWSMA-KWE-Z001")
      (footprint "easyedapro:SMA-TH_BWSMA-KWE-Z001")
      (fields (field (name "Manufacturer") "BAT WIRELESS(蝙蝠无线)"))
      (libsource (lib "easyedapro") (part "BWSMA-KWE-Z001"))
    )
    (comp (ref "U5")
      (value "MPU6050")
      (footprint "easyedapro:QFN-24_L4.0-W4.0-P0.50-BL")
      (libsource (lib "easyedapro") (part "MPU6050_C9900042518"))
    )
    (comp (ref "U6")
      (value "W25Q32JVSSIQ")
      (footprint "easyedapro:SOIC-8_L5.3-W5.3-P1.27-LS8.0-BL")
      (description "接口类型:SPI;存储容量:32Mbit;")
      (fields (field (name "Manufacturer") "WINBOND(华邦)"))
      (libsource (lib "easyedapro") (part "W25Q32JVSSIQ"))
    )
    (comp (ref "U7")
      (value "ATGM336H-5N31")
      (footprint "easyedapro:GPSM-SMD_ATGM336H-TR")
      (description "卫星定位模块 GPS+BDS")
      (fields (field (name "Manufacturer") "杭州中科微"))
      (libsource (lib "easyedapro") (part "ATGM336H-5N31"))
    )
    (comp (ref "U8")
      (value "AT2659S")
      (footprint "easyedapro:SOT-23-6_L2.9-W1.6-P0.95-LS2.8-BR")
      (description "电源电压:1.4V~3.6V;供电电流:4.4mA;增益:20dB;P1dB:-15dBm;噪声系数:0.8dB;")
      (fields (field (name "Manufacturer") "杭州中科微"))
      (libsource (lib "easyedapro") (part "AT2659S"))
    )
    (comp (ref "C40")
      (value "10nF")
      (footprint "easyedapro:C0805")
      (description "容值:100nF;精度:±10%;额定电压:100V;材质(温度系数):X7R;")
      (fields
        (field (name "Manufacturer Part") "CC0805KKX7R0BB104")
        (field (name "Manufacturer") "YAGEO(国巨)")
      )
      (libsource (lib "easyedapro") (part "CC0805KKX7R0BB104"))
    )
    (comp (ref "C41")
      (value "15pF")
      (footprint "easyedapro:C0805")
      (description "容值:100nF;精度:±10%;额定电压:100V;材质(温度系数):X7R;")
      (fields
        (field (name "Manufacturer Part") "CC0805KKX7R0BB104")
        (field (name "Manufacturer") "YAGEO(国巨)")
      )
      (libsource (lib "easyedapro") (part "CC0805KKX7R0BB104"))
    )
    (comp (ref "C42")
      (value "220uF")
      (footprint "easyedapro:CAP-SMD_BD8.0-L8.3-W8.3-LS9.3-FD")
      (description "容值:220uF;精度:±20%;额定电压:35V;纹波电流:195mA@120Hz;等效串联电阻:-;")
      (fields
        (field (name "Manufacturer Part") "RVT220UF35V67RV0024")
        (field (name "Manufacturer") "KNSCHA(科尼盛)")
      )
      (libsource (lib "easyedapro") (part "RVT220UF35V67RV0024"))
    )
    (comp (ref "C43")
      (value "100nF")
      (footprint "easyedapro:C0805")
      (description "容值:100nF;精度:±10%;额定电压:100V;材质(温度系数):X7R;")
      (fields
        (field (name "Manufacturer Part") "CC0805KKX7R0BB104")
        (field (name "Manufacturer") "YAGEO(国巨)")
      )
      (libsource (lib "easyedapro") (part "CC0805KKX7R0BB104"))
    )
    (comp (ref "C44")
      (value "100nF")
      (footprint "easyedapro:C0805")
      (description "容值:100nF;精度:±10%;额定电压:100V;材质(温度系数):X7R;")
      (fields
        (field (name "Manufacturer Part") "CC0805KKX7R0BB104")
        (field (name "Manufacturer") "YAGEO(国巨)")
      )
      (libsource (lib "easyedapro") (part "CC0805KKX7R0BB104"))
    )
    (comp (ref "C45")
      (value "220uF")
      (footprint "easyedapro:CAP-SMD_BD8.0-L8.3-W8.3-LS9.3-FD")
      (description "容值:220uF;精度:±20%;额定电压:35V;纹波电流:195mA@120Hz;等效串联电阻:-;")
      (fields
        (field (name "Manufacturer Part") "RVT220UF35V67RV0024")
        (field (name "Manufacturer") "KNSCHA(科尼盛)")
      )
      (libsource (lib "easyedapro") (part "RVT220UF35V67RV0024"))
    )
    (comp (ref "C46")
      (value "100nF")
      (footprint "easyedapro:C0805")
      (description "容值:100nF;精度:±10%;额定电压:100V;材质(温度系数):X7R;")
      (fields
        (field (name "Manufacturer Part") "CC0805KKX7R0BB104")
        (field (name "Manufacturer") "YAGEO(国巨)")
      )
      (libsource (lib "easyedapro") (part "CC0805KKX7R0BB104"))
    )
    (comp (ref "C47")
      (value "100nF")
      (footprint "easyedapro:C0805")
      (description "容值:100nF;精度:±10%;额定电压:100V;材质(温度系数):X7R;")
      (fields
        (field (name "Manufacturer Part") "CC0805KKX7R0BB104")
        (field (name "Manufacturer") "YAGEO(国巨)")
      )
      (libsource (lib "easyedapro") (part "CC0805KKX7R0BB104"))
    )
    (comp (ref "C48")
      (value "100nF")
      (footprint "easyedapro:C0805")
      (description "容值:100nF;精度:±10%;额定电压:100V;材质(温度系数):X7R;")
      (fields
        (field (name "Manufacturer Part") "CC0805KKX7R0BB104")
        (field (name "Manufacturer") "YAGEO(国巨)")
      )
      (libsource (lib "easyedapro") (part "CC0805KKX7R0BB104"))
    )
    (comp (ref "C49")
      (value "100nF")
      (footprint "easyedapro:C0805")
      (description "容值:100nF;精度:±10%;额定电压:100V;材质(温度系数):X7R;")
      (fields
        (field (name "Manufacturer Part") "CC0805KKX7R0BB104")
        (field (name "Manufacturer") "YAGEO(国巨)")
      )
      (libsource (lib "easyedapro") (part "CC0805KKX7R0BB104"))
    )
    (comp (ref "C50")
      (value "22uF")
      (footprint "easyedapro:CASE-A_3216")
      (description "容值:22uF;精度:±10%;额定电压:10V;等效串联电阻:3Ω@100kHz;")
      (fields (field (name "Manufacturer Part") "TAJA226K010RNJ") (field (name "Manufacturer") "Kyocera AVX"))
      (libsource (lib "easyedapro") (part "TAJA226K010RNJ"))
    )
    (comp (ref "C51")
      (value "22uF")
      (footprint "easyedapro:CASE-A_3216")
      (description "容值:22uF;精度:±10%;额定电压:10V;等效串联电阻:3Ω@100kHz;")
      (fields (field (name "Manufacturer Part") "TAJA226K010RNJ") (field (name "Manufacturer") "Kyocera AVX"))
      (libsource (lib "easyedapro") (part "TAJA226K010RNJ"))
    )
    (comp (ref "C52")
      (value "100nF")
      (footprint "easyedapro:C0805")
      (description "容值:100nF;精度:±10%;额定电压:100V;材质(温度系数):X7R;")
      (fields
        (field (name "Manufacturer Part") "CC0805KKX7R0BB104")
        (field (name "Manufacturer") "YAGEO(国巨)")
      )
      (libsource (lib "easyedapro") (part "CC0805KKX7R0BB104"))
    )
    (comp (ref "C53")
      (value "10nF")
      (footprint "easyedapro:C0805")
      (description "容值:100nF;精度:±10%;额定电压:100V;材质(温度系数):X7R;")
      (fields
        (field (name "Manufacturer Part") "CC0805KKX7R0BB104")
        (field (name "Manufacturer") "YAGEO(国巨)")
      )
      (libsource (lib "easyedapro") (part "CC0805KKX7R0BB104"))
    )
    (comp (ref "C54")
      (value "10nF")
      (footprint "easyedapro:C0805")
      (description "容值:100nF;精度:±10%;额定电压:100V;材质(温度系数):X7R;")
      (fields
        (field (name "Manufacturer Part") "CC0805KKX7R0BB104")
        (field (name "Manufacturer") "YAGEO(国巨)")
      )
      (libsource (lib "easyedapro") (part "CC0805KKX7R0BB104"))
    )
    (comp (ref "CN7")
      (value "ZX-XH2.54-2PZZ")
      (footprint "easyedapro:CONN-TH_2P-P2.50_HX25003-2A")
      (fields (field (name "Manufacturer") "Megastar(兆星)"))
      (libsource (lib "easyedapro") (part "ZX-XH2.54-2PZZ"))
    )
    (comp (ref "D5")
      (value "SS34")
      (footprint "easyedapro:SMA_L4.3-W2.5-LS5.0-RD")
      (description "二极管配置:独立式;正向压降(Vf):550mV@3A;直流反向耐压(Vr):40V;平均整流电流(Io):3A;")
      (fields (field (name "Manufacturer") "TWGMC(台湾迪嘉)"))
      (libsource (lib "easyedapro") (part "SS34_C727060"))
    )
    (comp (ref "D6")
      (value "SS34")
      (footprint "easyedapro:SMA_L4.3-W2.5-LS5.0-RD")
      (description "二极管配置:独立式;正向压降(Vf):550mV@3A;直流反向耐压(Vr):40V;平均整流电流(Io):3A;")
      (fields (field (name "Manufacturer") "TWGMC(台湾迪嘉)"))
      (libsource (lib "easyedapro") (part "SS34_C727060"))
    )
    (comp (ref "D7")
      (value "SS34")
      (footprint "easyedapro:SMA_L4.3-W2.5-LS5.0-RD")
      (description "二极管配置:独立式;正向压降(Vf):550mV@3A;直流反向耐压(Vr):40V;平均整流电流(Io):3A;")
      (fields (field (name "Manufacturer") "TWGMC(台湾迪嘉)"))
      (libsource (lib "easyedapro") (part "SS34_C727060"))
    )
    (comp (ref "D8")
      (value "BZT52C3V3S")
      (footprint "easyedapro:SOD-323_L1.8-W1.3-LS2.5-RD")
      (description "二极管配置:独立式;稳压值(标称值):3.3V;稳压值(范围):3.1V~3.5V;功率:200mW;精度:-;")
      (fields (field (name "Manufacturer") "LGE(鲁光)"))
      (libsource (lib "easyedapro") (part "BZT52C3V3S_C545302"))
    )
    (comp (ref "J1") (value "~") (footprint "easyedapro:M2螺丝") (libsource (lib "easyedapro") (part "螺丝孔")))
    (comp (ref "J2") (value "~") (footprint "easyedapro:M2螺丝") (libsource (lib "easyedapro") (part "螺丝孔")))
    (comp (ref "J3") (value "~") (footprint "easyedapro:M2螺丝") (libsource (lib "easyedapro") (part "螺丝孔")))
    (comp (ref "J4") (value "~") (footprint "easyedapro:M2螺丝") (libsource (lib "easyedapro") (part "螺丝孔")))
    (comp (ref "L2")
      (value "10uH")
      (footprint "easyedapro:IND-SMD_L7.3-W6.8")
      (description "电感值:10uH;精度:±20%;额定电流:4.5A;饱和电流(Isat):5.5A;类型:一体成型电感;")
      (fields (field (name "Manufacturer Part") "FXL0630-100-M") (field (name "Manufacturer") "cjiang(长江微电)"))
      (libsource (lib "easyedapro") (part "FXL0630-100-M"))
    )
    (comp (ref "PR1")
      (value "10K")
      (footprint "easyedapro:R_3386P")
      (libsource (lib "easyedapro") (part "3386P-1-103LF"))
    )
    (comp (ref "R24") (value "ADJ") (footprint "easyedapro:R0805") (libsource (lib "easyedapro") (part "电阻")))
    (comp (ref "R25") (value "10K") (footprint "easyedapro:R0805") (libsource (lib "easyedapro") (part "电阻")))
    (comp (ref "R26") (value "ADJ") (footprint "easyedapro:R0805") (libsource (lib "easyedapro") (part "电阻")))
    (comp (ref "R27") (value "47K") (footprint "easyedapro:R0805") (libsource (lib "easyedapro") (part "电阻")))
    (comp (ref "R28") (value "27K") (footprint "easyedapro:R0805") (libsource (lib "easyedapro") (part "电阻")))
    (comp (ref "R29")
      (value "5.1K")
      (footprint "easyedapro:R0805")
      (libsource (lib "easyedapro") (part "电阻"))
    )
    (comp (ref "R30")
      (value "5.1K")
      (footprint "easyedapro:R0805")
      (libsource (lib "easyedapro") (part "电阻"))
    )
    (comp (ref "R31") (value "10K") (footprint "easyedapro:R0805") (libsource (lib "easyedapro") (part "电阻")))
    (comp (ref "R32") (value "2K") (footprint "easyedapro:R0805") (libsource (lib "easyedapro") (part "电阻")))
    (comp (ref "R33") (value "10K") (footprint "easyedapro:R0805") (libsource (lib "easyedapro") (part "电阻")))
    (comp (ref "R34") (value "2K") (footprint "easyedapro:R0805") (libsource (lib "easyedapro") (part "电阻")))
    (comp (ref "U9") (value "X3DC") (libsource (lib "easyedapro") (part "X3DC")))
    (comp (ref "U10")
      (value "XC6206J332MR-G")
      (footprint "easyedapro:SOT-25_L3.0-W1.6-P0.95-LS2.8-BR")
      (description "输出类型:固定;最大输入电压:6V;输出电压:3.3V;最大输出电流:200mA;电源纹波抑制比(PSRR):-;输出极性:正极;")
      (fields (field (name "Manufacturer") "TOREX(特瑞仕)"))
      (libsource (lib "easyedapro") (part "XC6206J332MR-G"))
    )
    (comp (ref "U14")
      (value "GS8552-SR")
      (footprint "easyedapro:SOIC-8_L4.9-W3.9-P1.27-LS6.0-BL")
      (description "放大器数:双路;增益带宽积(GBP):1.8MHz;压摆率(SR):0.95V/us;")
      (fields (field (name "Manufacturer") "Gainsil(聚洵)"))
      (libsource (lib "easyedapro") (part "GS8552-SR"))
    )
    (comp (ref "USB1")
      (value "TYPE-C 16PIN 2MD(073)")
      (footprint "easyedapro:USB-C-SMD_TYPE-C-6PIN-2MD-073")
      (description "连接器类型:Type-C;标准:-;公母:母;端口数量:1;触点数量:16P;安装方式:卧贴;额定电流 - 电源:5A;工作温度范围:-25°C~+85°C;")
      (fields (field (name "Manufacturer") "SHOU HAN(首韩)"))
      (libsource (lib "easyedapro") (part "TYPE-C 16PIN 2MD(073)"))
    )
    (comp (ref "C55")
      (value "100nF")
      (footprint "easyedapro:C0805")
      (description "容值:100nF;精度:±10%;额定电压:100V;材质(温度系数):X7R;")
      (fields
        (field (name "Manufacturer Part") "CC0805KKX7R0BB104")
        (field (name "Manufacturer") "YAGEO(国巨)")
      )
      (libsource (lib "easyedapro") (part "CC0805KKX7R0BB104"))
    )
    (comp (ref "C56")
      (value "10nF")
      (footprint "easyedapro:C0805")
      (description "容值:100nF;精度:±10%;额定电压:100V;材质(温度系数):X7R;")
      (fields
        (field (name "Manufacturer Part") "CC0805KKX7R0BB104")
        (field (name "Manufacturer") "YAGEO(国巨)")
      )
      (libsource (lib "easyedapro") (part "CC0805KKX7R0BB104"))
    )
    (comp (ref "C57")
      (value "20pF")
      (footprint "easyedapro:C0805")
      (description "容值:100nF;精度:±10%;额定电压:100V;材质(温度系数):X7R;")
      (fields
        (field (name "Manufacturer Part") "CC0805KKX7R0BB104")
        (field (name "Manufacturer") "YAGEO(国巨)")
      )
      (libsource (lib "easyedapro") (part "CC0805KKX7R0BB104"))
    )
    (comp (ref "C58")
      (value "20pF")
      (footprint "easyedapro:C0805")
      (description "容值:100nF;精度:±10%;额定电压:100V;材质(温度系数):X7R;")
      (fields
        (field (name "Manufacturer Part") "CC0805KKX7R0BB104")
        (field (name "Manufacturer") "YAGEO(国巨)")
      )
      (libsource (lib "easyedapro") (part "CC0805KKX7R0BB104"))
    )
    (comp (ref "C59")
      (value "100nF")
      (footprint "easyedapro:C0805")
      (description "容值:100nF;精度:±10%;额定电压:100V;材质(温度系数):X7R;")
      (fields
        (field (name "Manufacturer Part") "CC0805KKX7R0BB104")
        (field (name "Manufacturer") "YAGEO(国巨)")
      )
      (libsource (lib "easyedapro") (part "CC0805KKX7R0BB104"))
    )
    (comp (ref "C60")
      (value "100nF")
      (footprint "easyedapro:C0805")
      (description "容值:100nF;精度:±10%;额定电压:100V;材质(温度系数):X7R;")
      (fields
        (field (name "Manufacturer Part") "CC0805KKX7R0BB104")
        (field (name "Manufacturer") "YAGEO(国巨)")
      )
      (libsource (lib "easyedapro") (part "CC0805KKX7R0BB104"))
    )
    (comp (ref "C61")
      (value "100nF")
      (footprint "easyedapro:C0805")
      (description "容值:100nF;精度:±10%;额定电压:100V;材质(温度系数):X7R;")
      (fields
        (field (name "Manufacturer Part") "CC0805KKX7R0BB104")
        (field (name "Manufacturer") "YAGEO(国巨)")
      )
      (libsource (lib "easyedapro") (part "CC0805KKX7R0BB104"))
    )
    (comp (ref "C62")
      (value "100nF")
      (footprint "easyedapro:C0805")
      (description "容值:100nF;精度:±10%;额定电压:100V;材质(温度系数):X7R;")
      (fields
        (field (name "Manufacturer Part") "CC0805KKX7R0BB104")
        (field (name "Manufacturer") "YAGEO(国巨)")
      )
      (libsource (lib "easyedapro") (part "CC0805KKX7R0BB104"))
    )
    (comp (ref "H2")
      (value "~")
      (footprint "easyedapro:HDR-TH_4P-P2.54-V-M")
      (libsource (lib "easyedapro") (part "PZ254V-11-04P"))
    )
    (comp (ref "LED2")
      (value "~")
      (footprint "easyedapro:LED_0805")
      (libsource (lib "easyedapro") (part "LED_G"))
    )
    (comp (ref "LED3")
      (value "~")
      (footprint "easyedapro:LED_0805")
      (libsource (lib "easyedapro") (part "LED_G"))
    )
    (comp (ref "LED4")
      (value "~")
      (footprint "easyedapro:LED_0805")
      (libsource (lib "easyedapro") (part "LED_G"))
    )
    (comp (ref "LED5")
      (value "~")
      (footprint "easyedapro:LED_0805")
      (libsource (lib "easyedapro") (part "LED_G"))
    )
    (comp (ref "PR2")
      (value "10K")
      (footprint "easyedapro:R_3386P")
      (libsource (lib "easyedapro") (part "3386P-1-103LF"))
    )
    (comp (ref "R35")
      (value "300R")
      (footprint "easyedapro:R0805")
      (libsource (lib "easyedapro") (part "电阻"))
    )
    (comp (ref "R36")
      (value "300R")
      (footprint "easyedapro:R0805")
      (libsource (lib "easyedapro") (part "电阻"))
    )
    (comp (ref "R37")
      (value "300R")
      (footprint "easyedapro:R0805")
      (libsource (lib "easyedapro") (part "电阻"))
    )
    (comp (ref "R38")
      (value "300R")
      (footprint "easyedapro:R0805")
      (libsource (lib "easyedapro") (part "电阻"))
    )
    (comp (ref "R39") (value "10K") (footprint "easyedapro:R0805") (libsource (lib "easyedapro") (part "电阻")))
    (comp (ref "R40") (value "10K") (footprint "easyedapro:R0805") (libsource (lib "easyedapro") (part "电阻")))
    (comp (ref "R41") (value "10K") (footprint "easyedapro:R0805") (libsource (lib "easyedapro") (part "电阻")))
    (comp (ref "R42") (value "0R") (footprint "easyedapro:R0805") (libsource (lib "easyedapro") (part "电阻")))
    (comp (ref "R43")
      (value "100R")
      (footprint "easyedapro:R0805")
      (libsource (lib "easyedapro") (part "电阻"))
    )
    (comp (ref "R44") (value "1M") (footprint "easyedapro:R0805") (libsource (lib "easyedapro") (part "电阻")))
    (comp (ref "R45")
      (value "100R")
      (footprint "easyedapro:R0805")
      (libsource (lib "easyedapro") (part "电阻"))
    )
    (comp (ref "U11")
      (value "GD32F307RCT6")
      (footprint "easyedapro:LQFP-64_L10.0-W10.0-P0.50-LS12.0-BL")
      (description "CPU内核:CM4;程序存储容量:256KB;RAM总容量:96KB;GPIO端口数量:51;工作电压范围:-;CPU最大主频:120MHz;程序存储器类型:FLASH;")
      (fields (field (name "Manufacturer") "GigaDevice(兆易创新)"))
      (libsource (lib "easyedapro") (part "GD32F307RCT6"))
    )
    (comp (ref "X1")
      (value "25MHz")
      (footprint "easyedapro:HC-49S_L11.4-W4.8")
      (description "晶振类型:贴片晶振;频率:25MHz;常温频差:±20ppm;外接负载电容:20pF;频率稳定度(全温):±30ppm;")
      (fields (field (name "Manufacturer Part") "X49SM25MSD2SC") (field (name "Manufacturer") "YXC(扬兴晶振)"))
      (libsource (lib "easyedapro") (part "X49SM25MSD2SC"))
    )
  )
  (nets
    (net (code "1") (name "+5V0") (class "Default")
      (node (ref "C27") (pin "2") (pinfunction "2_2") (pintype "input"))
      (node (ref "C45") (pin "1") (pinfunction "1_1") (pintype "input"))
      (node (ref "C46") (pin "2") (pinfunction "2_2") (pintype "input"))
      (node (ref "C50") (pin "1") (pinfunction "1_1") (pintype "input"))
      (node (ref "C52") (pin "1") (pinfunction "1_1") (pintype "input"))
      (node (ref "C53") (pin "1") (pinfunction "1_1") (pintype "input"))
      (node (ref "D7") (pin "1") (pinfunction "C_1") (pintype "unspecified"))
      (node (ref "L2") (pin "2") (pinfunction "2_2") (pintype "unspecified"))
      (node (ref "Q1") (pin "2") (pinfunction "S_2") (pintype "unspecified"))
      (node (ref "R26") (pin "2") (pinfunction "2_2") (pintype "input"))
      (node (ref "R9") (pin "2") (pinfunction "2_2") (pintype "input"))
      (node (ref "U10") (pin "2") (pinfunction "VIN_2") (pintype "unspecified"))
    )
    (net (code "2") (name "4G_PWR") (class "Default")
      (node (ref "R12") (pin "2") (pinfunction "2_2") (pintype "input"))
      (node (ref "U11") (pin "41") (pinfunction "PA8_41") (pintype "unspecified"))
    )
    (net (code "3") (name "4G_RXD") (class "Default")
      (node (ref "R10") (pin "1") (pinfunction "1_1") (pintype "input"))
      (node (ref "U11") (pin "42") (pinfunction "PA9_42") (pintype "unspecified"))
    )
    (net (code "4") (name "4G_TXD") (class "Default")
      (node (ref "R11") (pin "1") (pinfunction "1_1") (pintype "input"))
      (node (ref "U11") (pin "43") (pinfunction "PA10_43") (pintype "unspecified"))
    )
    (net (code "5") (name "ADC_MOT_TEMP1") (class "Default")
      (node (ref "C4") (pin "2") (pinfunction "2_2") (pintype "input"))
      (node (ref "C5") (pin "2") (pinfunction "2_2") (pintype "input"))
      (node (ref "D2") (pin "2") (pinfunction "2_2") (pintype "unspecified"))
      (node (ref "U11") (pin "8") (pinfunction "PC0_8") (pintype "unspecified"))
      (node (ref "U12") (pin "1") (pinfunction "OUT_1") (pintype "output"))
      (node (ref "U12") (pin "2") (pinfunction "INVERTING_INPUT_2") (pintype "unspecified"))
    )
    (net (code "6") (name "ADC_MOT_TEMP2") (class "Default")
      (node (ref "C11") (pin "2") (pinfunction "2_2") (pintype "input"))
      (node (ref "C12") (pin "2") (pinfunction "2_2") (pintype "input"))
      (node (ref "D4") (pin "2") (pinfunction "2_2") (pintype "unspecified"))
      (node (ref "U11") (pin "9") (pinfunction "PC1_9") (pintype "unspecified"))
      (node (ref "U12") (pin "6") (pinfunction "INVERTING_INPUT_6") (pintype "unspecified"))
      (node (ref "U12") (pin "7") (pinfunction "OUT_7") (pintype "output"))
    )
    (net (code "7") (name "ADC_MOT_TEMP3") (class "Default")
      (node (ref "C10") (pin "2") (pinfunction "2_2") (pintype "input"))
      (node (ref "C9") (pin "2") (pinfunction "2_2") (pintype "input"))
      (node (ref "D3") (pin "2") (pinfunction "2_2") (pintype "unspecified"))
      (node (ref "U11") (pin "10") (pinfunction "PC2_10") (pintype "unspecified"))
      (node (ref "U13") (pin "6") (pinfunction "INVERTING_INPUT_6") (pintype "unspecified"))
      (node (ref "U13") (pin "7") (pinfunction "OUT_7") (pintype "output"))
    )
    (net (code "8") (name "ADC_MOT_TEMP4") (class "Default")
      (node (ref "C3") (pin "2") (pinfunction "2_2") (pintype "input"))
      (node (ref "C7") (pin "2") (pinfunction "2_2") (pintype "input"))
      (node (ref "D1") (pin "2") (pinfunction "2_2") (pintype "unspecified"))
      (node (ref "U11") (pin "11") (pinfunction "PC3_11") (pintype "unspecified"))
      (node (ref "U13") (pin "1") (pinfunction "OUT_1") (pintype "output"))
      (node (ref "U13") (pin "2") (pinfunction "INVERTING_INPUT_2") (pintype "unspecified"))
    )
    (net (code "9") (name "BAT_ADC") (class "Default")
      (node (ref "U11") (pin "24") (pinfunction "PC4_24") (pintype "unspecified"))
      (node (ref "U14") (pin "6") (pinfunction "INVERTING_INPUT_6") (pintype "unspecified"))
      (node (ref "U14") (pin "7") (pinfunction "OUT_7") (pintype "output"))
    )
    (net (code "10") (name "BAT_INT") (class "Default")
      (node (ref "U11") (pin "50") (pinfunction "PA15_50") (pintype "unspecified"))
      (node (ref "U14") (pin "1") (pinfunction "OUT_1") (pintype "output"))
    )
    (net (code "11") (name "GND") (class "Default")
      (node (ref "BT1") (pin "2") (pinfunction "2_2") (pintype "input"))
      (node (ref "C1") (pin "1") (pinfunction "1_1") (pintype "input"))
      (node (ref "C10") (pin "1") (pinfunction "1_1") (pintype "input"))
      (node (ref "C11") (pin "1") (pinfunction "1_1") (pintype "input"))
      (node (ref "C12") (pin "1") (pinfunction "1_1") (pintype "input"))
      (node (ref "C13") (pin "1") (pinfunction "1_1") (pintype "input"))
      (node (ref "C14") (pin "1") (pinfunction "1_1") (pintype "input"))
      (node (ref "C15") (pin "1") (pinfunction "1_1") (pintype "input"))
      (node (ref "C16") (pin "2") (pinfunction "2_2") (pintype "input"))
      (node (ref "C17") (pin "1") (pinfunction "1_1") (pintype "input"))
      (node (ref "C18") (pin "1") (pinfunction "1_1") (pintype "input"))
      (node (ref "C19") (pin "2") (pinfunction "2_2") (pintype "input"))
      (node (ref "C2") (pin "1") (pinfunction "1_1") (pintype "input"))
      (node (ref "C20") (pin "1") (pinfunction "1_1") (pintype "input"))
      (node (ref "C21") (pin "1") (pinfunction "1_1") (pintype "input"))
      (node (ref "C22") (pin "2") (pinfunction "2_2") (pintype "input"))
      (node (ref "C23") (pin "1") (pinfunction "1_1") (pintype "input"))
      (node (ref "C24") (pin "1") (pinfunction "1_1") (pintype "input"))
      (node (ref "C25") (pin "2") (pinfunction "2_2") (pintype "input"))
      (node (ref "C26") (pin "1") (pinfunction "1_1") (pintype "input"))
      (node (ref "C28") (pin "2") (pinfunction "2_2") (pintype "input"))
      (node (ref "C29") (pin "2") (pinfunction "2_2") (pintype "input"))
      (node (ref "C3") (pin "1") (pinfunction "1_1") (pintype "input"))
      (node (ref "C30") (pin "2") (pinfunction "2_2") (pintype "input"))
      (node (ref "C31") (pin "1") (pinfunction "1_1") (pintype "input"))
      (node (ref "C32") (pin "2") (pinfunction "2_2") (pintype "input"))
      (node (ref "C33") (pin "1") (pinfunction "1_1") (pintype "input"))
      (node (ref "C34") (pin "2") (pinfunction "2_2") (pintype "input"))
      (node (ref "C35") (pin "1") (pinfunction "1_1") (pintype "input"))
      (node (ref "C36") (pin "2") (pinfunction "2_2") (pintype "input"))
      (node (ref "C38") (pin "1") (pinfunction "1_1") (pintype "input"))
      (node (ref "C39") (pin "1") (pinfunction "1_1") (pintype "input"))
      (node (ref "C4") (pin "1") (pinfunction "1_1") (pintype "input"))
      (node (ref "C40") (pin "2") (pinfunction "2_2") (pintype "input"))
      (node (ref "C41") (pin "1") (pinfunction "1_1") (pintype "input"))
      (node (ref "C42") (pin "2") (pinfunction "2_2") (pintype "input"))
      (node (ref "C43") (pin "2") (pinfunction "2_2") (pintype "input"))
      (node (ref "C45") (pin "2") (pinfunction "2_2") (pintype "input"))
      (node (ref "C46") (pin "1") (pinfunction "1_1") (pintype "input"))
      (node (ref "C47") (pin "2") (pinfunction "2_2") (pintype "input"))
      (node (ref "C48") (pin "2") (pinfunction "2_2") (pintype "input"))
      (node (ref "C49") (pin "2") (pinfunction "2_2") (pintype "input"))
      (node (ref "C5") (pin "1") (pinfunction "1_1") (pintype "input"))
      (node (ref "C50") (pin "2") (pinfunction "2_2") (pintype "input"))
      (node (ref "C51") (pin "2") (pinfunction "2_2") (pintype "input"))
      (node (ref "C52") (pin "2") (pinfunction "2_2") (pintype "input"))
      (node (ref "C53") (pin "2") (pinfunction "2_2") (pintype "input"))
      (node (ref "C54") (pin "2") (pinfunction "2_2") (pintype "input"))
      (node (ref "C55") (pin "2") (pinfunction "2_2") (pintype "input"))
      (node (ref "C56") (pin "1") (pinfunction "1_1") (pintype "input"))
      (node (ref "C57") (pin "1") (pinfunction "1_1") (pintype "input"))
      (node (ref "C58") (pin "1") (pinfunction "1_1") (pintype "input"))
      (node (ref "C59") (pin "2") (pinfunction "2_2") (pintype "input"))
      (node (ref "C6") (pin "1") (pinfunction "1_1") (pintype "input"))
      (node (ref "C60") (pin "2") (pinfunction "2_2") (pintype "input"))
      (node (ref "C61") (pin "2") (pinfunction "2_2") (pintype "input"))
      (node (ref "C62") (pin "2") (pinfunction "2_2") (pintype "input"))
      (node (ref "C7") (pin "1") (pinfunction "1_1") (pintype "input"))
      (node (ref "C8") (pin "1") (pinfunction "1_1") (pintype "input"))
      (node (ref "C9") (pin "1") (pinfunction "1_1") (pintype "input"))
      (node (ref "CN1") (pin "2") (pinfunction "2_2") (pintype "unspecified"))
      (node (ref "CN2") (pin "2") (pinfunction "2_2") (pintype "unspecified"))
      (node (ref "CN3") (pin "2") (pinfunction "2_2") (pintype "unspecified"))
      (node (ref "CN4") (pin "2") (pinfunction "2_2") (pintype "unspecified"))
      (node (ref "CN5") (pin "1") (pinfunction "1_1") (pintype "unspecified"))
      (node (ref "CN5") (pin "6") (pinfunction "6_6") (pintype "unspecified"))
      (node (ref "CN5") (pin "7") (pinfunction "7_7") (pintype "unspecified"))
      (node (ref "CN6") (pin "10") (pinfunction "10_10") (pintype "unspecified"))
      (node (ref "CN6") (pin "8") (pinfunction "8_8") (pintype "unspecified"))
      (node (ref "CN6") (pin "9") (pinfunction "9_9") (pintype "unspecified"))
      (node (ref "CN7") (pin "2") (pinfunction "2_2") (pintype "unspecified"))
      (node (ref "D1") (pin "1") (pinfunction "1_1") (pintype "unspecified"))
      (node (ref "D2") (pin "1") (pinfunction "1_1") (pintype "unspecified"))
      (node (ref "D3") (pin "1") (pinfunction "1_1") (pintype "unspecified"))
      (node (ref "D4") (pin "1") (pinfunction "1_1") (pintype "unspecified"))
      (node (ref "D6") (pin "2") (pinfunction "A_2") (pintype "unspecified"))
      (node (ref "D8") (pin "2") (pinfunction "A_2") (pintype "unspecified"))
      (node (ref "H1") (pin "4") (pinfunction "4_4") (pintype "unspecified"))
      (node (ref "H2") (pin "3") (pinfunction "3_3") (pintype "unspecified"))
      (node (ref "J1") (pin "1") (pinfunction "1_1") (pintype "input"))
      (node (ref "J2") (pin "1") (pinfunction "1_1") (pintype "input"))
      (node (ref "J3") (pin "1") (pinfunction "1_1") (pintype "input"))
      (node (ref "J4") (pin "1") (pinfunction "1_1") (pintype "input"))
      (node (ref "PR1") (pin "3") (pinfunction "3_3") (pintype "input"))
      (node (ref "PR2") (pin "1") (pinfunction "1_1") (pintype "input"))
      (node (ref "Q2") (pin "2") (pinfunction "E_2") (pintype "unspecified"))
      (node (ref "R1") (pin "1") (pinfunction "1_1") (pintype "input"))
      (node (ref "R13") (pin "1") (pinfunction "1_1") (pintype "input"))
      (node (ref "R19") (pin "1") (pinfunction "1_1") (pintype "input"))
      (node (ref "R2") (pin "1") (pinfunction "1_1") (pintype "input"))
      (node (ref "R24") (pin "1") (pinfunction "1_1") (pintype "input"))
      (node (ref "R27") (pin "2") (pinfunction "2_2") (pintype "input"))
      (node (ref "R29") (pin "2") (pinfunction "2_2") (pintype "input"))
      (node (ref "R3") (pin "1") (pinfunction "1_1") (pintype "input"))
      (node (ref "R30") (pin "2") (pinfunction "2_2") (pintype "input"))
      (node (ref "R32") (pin "1") (pinfunction "1_1") (pintype "input"))
      (node (ref "R34") (pin "2") (pinfunction "2_2") (pintype "input"))
      (node (ref "R39") (pin "1") (pinfunction "1_1") (pintype "input"))
      (node (ref "R4") (pin "1") (pinfunction "1_1") (pintype "input"))
      (node (ref "R5") (pin "2") (pinfunction "2_2") (pintype "input"))
      (node (ref "R6") (pin "2") (pinfunction "2_2") (pintype "input"))
      (node (ref "R7") (pin "2") (pinfunction "2_2") (pintype "input"))
      (node (ref "R8") (pin "2") (pinfunction "2_2") (pintype "input"))
      (node (ref "RF1") (pin "1") (pinfunction "1_1") (pintype "unspecified"))
      (node (ref "RF1") (pin "2") (pinfunction "2_2") (pintype "unspecified"))
      (node (ref "RF1") (pin "3") (pinfunction "3_3") (pintype "unspecified"))
      (node (ref "RF1") (pin "4") (pinfunction "4_4") (pintype "unspecified"))
      (node (ref "U1") (pin "1") (pinfunction "GND_1") (pintype "unspecified"))
      (node (ref "U1") (pin "9") (pinfunction "EP_9") (pintype "unspecified"))
      (node (ref "U10") (pin "4") (pinfunction "VSS_4") (pintype "unspecified"))
      (node (ref "U11") (pin "12") (pinfunction "VSSA_12") (pintype "unspecified"))
      (node (ref "U11") (pin "18") (pinfunction "VSS_4_18") (pintype "unspecified"))
      (node (ref "U11") (pin "31") (pinfunction "VSS_1_31") (pintype "unspecified"))
      (node (ref "U11") (pin "47") (pinfunction "VSS_2_47") (pintype "unspecified"))
      (node (ref "U11") (pin "63") (pinfunction "VSS_3_63") (pintype "unspecified"))
      (node (ref "U12") (pin "4") (pinfunction "-V_4") (pintype "unspecified"))
      (node (ref "U13") (pin "4") (pinfunction "-V_4") (pintype "unspecified"))
      (node (ref "U14") (pin "4") (pinfunction "-V_4") (pintype "unspecified"))
      (node (ref "U2") (pin "1") (pinfunction "GND_1") (pintype "unspecified"))
      (node (ref "U2") (pin "9") (pinfunction "EP_9") (pintype "unspecified"))
      (node (ref "U3") (pin "1") (pinfunction "GND_1") (pintype "unspecified"))
      (node (ref "U3") (pin "9") (pinfunction "EP_9") (pintype "unspecified"))
      (node (ref "U4") (pin "1") (pinfunction "GND_1") (pintype "unspecified"))
      (node (ref "U4") (pin "9") (pinfunction "EP_9") (pintype "unspecified"))
      (node (ref "U5") (pin "1") (pinfunction "CLKIN_1") (pintype "unspecified"))
      (node (ref "U5") (pin "11") (pinfunction "FSYNC_11") (pintype "unspecified"))
      (node (ref "U5") (pin "18") (pinfunction "GND_18") (pintype "unspecified"))
      (node (ref "U6") (pin "4") (pinfunction "GND_4") (pintype "unspecified"))
      (node (ref "U7") (pin "1") (pinfunction "GND_1") (pintype "unspecified"))
      (node (ref "U7") (pin "10") (pinfunction "GND_10") (pintype "unspecified"))
      (node (ref "U7") (pin "12") (pinfunction "GND_12") (pintype "unspecified"))
      (node (ref "U8") (pin "2") (pinfunction "GND_2") (pintype "unspecified"))
      (node (ref "U8") (pin "3") (pinfunction "GND_3") (pintype "unspecified"))
      (node (ref "U9") (pin "7") (pinfunction "GND_7") (pintype "input"))
      (node (ref "U9") (pin "9") (pinfunction "PAD_9") (pintype "input"))
      (node (ref "USB1") (pin "1") (pinfunction "GND_1") (pintype "unspecified"))
      (node (ref "USB1") (pin "12") (pinfunction "GND_12") (pintype "unspecified"))
      (node (ref "USB1") (pin "13") (pinfunction "SHELL_13") (pintype "unspecified"))
      (node (ref "USB1") (pin "14") (pinfunction "SHELL_14") (pintype "unspecified"))
    )
    (net (code "12") (name "GPS_PWR") (class "Default")
      (node (ref "U11") (pin "27") (pinfunction "PB1_27") (pintype "unspecified"))
      (node (ref "U7") (pin "5") (pinfunction "ON/OFF_5") (pintype "unspecified"))
    )
    (net (code "13") (name "GPS_RST") (class "Default")
      (node (ref "U11") (pin "26") (pinfunction "PB0_26") (pintype "unspecified"))
      (node (ref "U7") (pin "9") (pinfunction "NRESET_9") (pintype "unspecified"))
    )
    (net (code "14") (name "GPS_RXD") (class "Default")
      (node (ref "R22") (pin "1") (pinfunction "1_1") (pintype "input"))
      (node (ref "U11") (pin "29") (pinfunction "PB10_29") (pintype "unspecified"))
    )
    (net (code "15") (name "GPS_TXD") (class "Default")
      (node (ref "R21") (pin "1") (pinfunction "1_1") (pintype "input"))
      (node (ref "U11") (pin "30") (pinfunction "PB11_30") (pintype "unspecified"))
    )
    (net (code "16") (name "MM_CS") (class "Default")
      (node (ref "R20") (pin "1") (pinfunction "1_1") (pintype "input"))
      (node (ref "U11") (pin "39") (pinfunction "PC8_39") (pintype "unspecified"))
      (node (ref "U6") (pin "1") (pinfunction "CS#_1") (pintype "unspecified"))
    )
    (net (code "17") (name "Net-(C37-Pad1)") (class "Default")
      (node (ref "C37") (pin "1") (pinfunction "1_1") (pintype "input"))
      (node (ref "RF1") (pin "5") (pinfunction "5_5") (pintype "unspecified"))
    )
    (net (code "18") (name "Net-(C37-Pad2)") (class "Default")
      (node (ref "C37") (pin "2") (pinfunction "2_2") (pintype "input"))
      (node (ref "L1") (pin "2") (pinfunction "2_2") (pintype "input"))
    )
    (net (code "19") (name "Net-(C40-Pad1)") (class "Default")
      (node (ref "C40") (pin "1") (pinfunction "1_1") (pintype "input"))
      (node (ref "R28") (pin "2") (pinfunction "2_2") (pintype "input"))
    )
    (net (code "20") (name "Net-(CN5-Pad4)") (class "Default")
      (node (ref "CN5") (pin "4") (pinfunction "4_4") (pintype "unspecified"))
      (node (ref "R11") (pin "2") (pinfunction "2_2") (pintype "input"))
    )
    (net (code "21") (name "Net-(CN5-Pad5)") (class "Default")
      (node (ref "CN5") (pin "5") (pinfunction "5_5") (pintype "unspecified"))
      (node (ref "R10") (pin "2") (pinfunction "2_2") (pintype "input"))
    )
    (net (code "22") (name "Net-(D5-C)") (class "Default")
      (node (ref "C42") (pin "1") (pinfunction "1_1") (pintype "input"))
      (node (ref "C43") (pin "1") (pinfunction "1_1") (pintype "input"))
      (node (ref "D5") (pin "1") (pinfunction "C_1") (pintype "unspecified"))
      (node (ref "U9") (pin "2") (pinfunction "VIN_2") (pintype "input"))
      (node (ref "U9") (pin "3") (pinfunction "EN_3") (pintype "input"))
    )
    (net (code "23") (name "Net-(D6-C)") (class "Default")
      (node (ref "C44") (pin "1") (pinfunction "1_1") (pintype "input"))
      (node (ref "D6") (pin "1") (pinfunction "C_1") (pintype "unspecified"))
      (node (ref "L2") (pin "1") (pinfunction "1_1") (pintype "unspecified"))
      (node (ref "U9") (pin "8") (pinfunction "SW_8") (pintype "input"))
    )
    (net (code "24") (name "Net-(D8-C)") (class "Default")
      (node (ref "C48") (pin "1") (pinfunction "1_1") (pintype "input"))
      (node (ref "D8") (pin "1") (pinfunction "C_1") (pintype "unspecified"))
      (node (ref "R31") (pin "2") (pinfunction "2_2") (pintype "input"))
      (node (ref "R32") (pin "2") (pinfunction "2_2") (pintype "input"))
      (node (ref "U14") (pin "5") (pinfunction "NONINVERTING_INPUT_5") (pintype "unspecified"))
    )
    (net (code "25") (name "Net-(H2-Pad1)") (class "Default")
      (node (ref "H2") (pin "1") (pinfunction "1_1") (pintype "unspecified"))
      (node (ref "R43") (pin "1") (pinfunction "1_1") (pintype "input"))
    )
    (net (code "26") (name "Net-(H2-Pad4)") (class "Default")
      (node (ref "H2") (pin "4") (pinfunction "4_4") (pintype "unspecified"))
      (node (ref "R45") (pin "1") (pinfunction "1_1") (pintype "input"))
    )
    (net (code "27") (name "Net-(LED1-C)") (class "Default")
      (node (ref "LED1") (pin "1") (pinfunction "C_1") (pintype "input"))
      (node (ref "R23") (pin "1") (pinfunction "1_1") (pintype "input"))
    )
    (net (code "28") (name "Net-(LED2-A)") (class "Default")
      (node (ref "LED2") (pin "2") (pinfunction "A_2") (pintype "input"))
      (node (ref "R35") (pin "1") (pinfunction "1_1") (pintype "input"))
    )
    (net (code "29") (name "Net-(LED3-A)") (class "Default")
      (node (ref "LED3") (pin "2") (pinfunction "A_2") (pintype "input"))
      (node (ref "R36") (pin "1") (pinfunction "1_1") (pintype "input"))
    )
    (net (code "30") (name "Net-(LED4-A)") (class "Default")
      (node (ref "LED4") (pin "2") (pinfunction "A_2") (pintype "input"))
      (node (ref "R37") (pin "1") (pinfunction "1_1") (pintype "input"))
    )
    (net (code "31") (name "Net-(LED5-A)") (class "Default")
      (node (ref "LED5") (pin "2") (pinfunction "A_2") (pintype "input"))
      (node (ref "R38") (pin "1") (pinfunction "1_1") (pintype "input"))
    )
    (net (code "32") (name "Net-(PR2-Pad2)") (class "Default")
      (node (ref "PR2") (pin "2") (pinfunction "2_2") (pintype "input"))
      (node (ref "R41") (pin "1") (pinfunction "1_1") (pintype "input"))
    )
    (net (code "33") (name "Net-(Q1-D)") (class "Default")
      (node (ref "CN5") (pin "2") (pinfunction "2_2") (pintype "unspecified"))
      (node (ref "CN5") (pin "3") (pinfunction "3_3") (pintype "unspecified"))
      (node (ref "Q1") (pin "3") (pinfunction "D_3") (pintype "unspecified"))
    )
    (net (code "34") (name "Net-(Q1-G)") (class "Default")
      (node (ref "C27") (pin "1") (pinfunction "1_1") (pintype "input"))
      (node (ref "Q1") (pin "1") (pinfunction "G_1") (pintype "unspecified"))
      (node (ref "Q2") (pin "3") (pinfunction "C_3") (pintype "unspecified"))
      (node (ref "R9") (pin "1") (pinfunction "1_1") (pintype "input"))
    )
    (net (code "35") (name "Net-(Q2-B)") (class "Default")
      (node (ref "Q2") (pin "1") (pinfunction "B_1") (pintype "unspecified"))
      (node (ref "R12") (pin "1") (pinfunction "1_1") (pintype "input"))
      (node (ref "R13") (pin "2") (pinfunction "2_2") (pintype "input"))
    )
    (net (code "36") (name "Net-(R24-Pad2)") (class "Default")
      (node (ref "R24") (pin "2") (pinfunction "2_2") (pintype "input"))
      (node (ref "R25") (pin "1") (pinfunction "1_1") (pintype "input"))
    )
    (net (code "37") (name "Net-(U1-OUT1)") (class "Default")
      (node (ref "CN4") (pin "3") (pinfunction "3_3") (pintype "unspecified"))
      (node (ref "U1") (pin "6") (pinfunction "OUT1_6") (pintype "unspecified"))
    )
    (net (code "38") (name "Net-(U1-OUT2)") (class "Default")
      (node (ref "CN4") (pin "1") (pinfunction "1_1") (pintype "unspecified"))
      (node (ref "U1") (pin "8") (pinfunction "OUT2_8") (pintype "unspecified"))
    )
    (net (code "39") (name "Net-(U1-RS)") (class "Default")
      (node (ref "R5") (pin "1") (pinfunction "1_1") (pintype "input"))
      (node (ref "U1") (pin "7") (pinfunction "RS_7") (pintype "unspecified"))
    )
    (net (code "40") (name "Net-(U2-OUT1)") (class "Default")
      (node (ref "CN1") (pin "3") (pinfunction "3_3") (pintype "unspecified"))
      (node (ref "U2") (pin "6") (pinfunction "OUT1_6") (pintype "unspecified"))
    )
    (net (code "41") (name "Net-(U2-OUT2)") (class "Default")
      (node (ref "CN1") (pin "1") (pinfunction "1_1") (pintype "unspecified"))
      (node (ref "U2") (pin "8") (pinfunction "OUT2_8") (pintype "unspecified"))
    )
    (net (code "42") (name "Net-(U2-RS)") (class "Default")
      (node (ref "R6") (pin "1") (pinfunction "1_1") (pintype "input"))
      (node (ref "U2") (pin "7") (pinfunction "RS_7") (pintype "unspecified"))
    )
    (net (code "43") (name "Net-(U3-OUT1)") (class "Default")
      (node (ref "CN3") (pin "3") (pinfunction "3_3") (pintype "unspecified"))
      (node (ref "U3") (pin "6") (pinfunction "OUT1_6") (pintype "unspecified"))
    )
    (net (code "44") (name "Net-(U3-OUT2)") (class "Default")
      (node (ref "CN3") (pin "1") (pinfunction "1_1") (pintype "unspecified"))
      (node (ref "U3") (pin "8") (pinfunction "OUT2_8") (pintype "unspecified"))
    )
    (net (code "45") (name "Net-(U3-RS)") (class "Default")
      (node (ref "R7") (pin "1") (pinfunction "1_1") (pintype "input"))
      (node (ref "U3") (pin "7") (pinfunction "RS_7") (pintype "unspecified"))
    )
    (net (code "46") (name "Net-(U4-OUT1)") (class "Default")
      (node (ref "CN2") (pin "3") (pinfunction "3_3") (pintype "unspecified"))
      (node (ref "U4") (pin "6") (pinfunction "OUT1_6") (pintype "unspecified"))
    )
    (net (code "47") (name "Net-(U4-OUT2)") (class "Default")
      (node (ref "CN2") (pin "1") (pinfunction "1_1") (pintype "unspecified"))
      (node (ref "U4") (pin "8") (pinfunction "OUT2_8") (pintype "unspecified"))
    )
    (net (code "48") (name "Net-(U4-RS)") (class "Default")
      (node (ref "R8") (pin "1") (pinfunction "1_1") (pintype "input"))
      (node (ref "U4") (pin "7") (pinfunction "RS_7") (pintype "unspecified"))
    )
    (net (code "49") (name "Net-(U5-AD0)") (class "Default")
      (node (ref "R19") (pin "2") (pinfunction "2_2") (pintype "input"))
      (node (ref "U5") (pin "9") (pinfunction "AD0_9") (pintype "unspecified"))
    )
    (net (code "50") (name "Net-(U5-AUX_CL)") (class "Default")
      (node (ref "H1") (pin "2") (pinfunction "2_2") (pintype "unspecified"))
      (node (ref "U5") (pin "7") (pinfunction "AUX_CL_7") (pintype "unspecified"))
    )
    (net (code "51") (name "Net-(U5-AUX_DA)") (class "Default")
      (node (ref "H1") (pin "3") (pinfunction "3_3") (pintype "unspecified"))
      (node (ref "U5") (pin "6") (pinfunction "AUX_DA_6") (pintype "unspecified"))
    )
    (net (code "52") (name "Net-(U5-CPOUT)") (class "Default")
      (node (ref "C31") (pin "2") (pinfunction "2_2") (pintype "input"))
      (node (ref "U5") (pin "20") (pinfunction "CPOUT_20") (pintype "unspecified"))
    )
    (net (code "53") (name "Net-(U5-REGOUT)") (class "Default")
      (node (ref "C32") (pin "1") (pinfunction "1_1") (pintype "input"))
      (node (ref "U5") (pin "10") (pinfunction "REGOUT_10") (pintype "unspecified"))
    )
    (net (code "54") (name "Net-(U7-1PPS)") (class "Default")
      (node (ref "R23") (pin "2") (pinfunction "2_2") (pintype "input"))
      (node (ref "U7") (pin "4") (pinfunction "1PPS_4") (pintype "unspecified"))
    )
    (net (code "55") (name "Net-(U7-RF_IN)") (class "Default")
      (node (ref "U7") (pin "11") (pinfunction "RF_IN_11") (pintype "unspecified"))
      (node (ref "U8") (pin "4") (pinfunction "RFOUT_4") (pintype "unspecified"))
    )
    (net (code "56") (name "Net-(U7-RXD)") (class "Default")
      (node (ref "R22") (pin "2") (pinfunction "2_2") (pintype "input"))
      (node (ref "U7") (pin "3") (pinfunction "RXD_3") (pintype "unspecified"))
    )
    (net (code "57") (name "Net-(U7-TXD)") (class "Default")
      (node (ref "R21") (pin "2") (pinfunction "2_2") (pintype "input"))
      (node (ref "U7") (pin "2") (pinfunction "TXD_2") (pintype "unspecified"))
    )
    (net (code "58") (name "Net-(U7-VBAT)") (class "Default")
      (node (ref "BT1") (pin "1") (pinfunction "1_1") (pintype "input"))
      (node (ref "U7") (pin "6") (pinfunction "VBAT_6") (pintype "unspecified"))
    )
    (net (code "59") (name "Net-(U7-VCC_RF)") (class "Default")
      (node (ref "C35") (pin "2") (pinfunction "2_2") (pintype "input"))
      (node (ref "U7") (pin "14") (pinfunction "VCC_RF_14") (pintype "unspecified"))
    )
    (net (code "60") (name "Net-(U8-RFIN)") (class "Default")
      (node (ref "L1") (pin "1") (pinfunction "1_1") (pintype "input"))
      (node (ref "U8") (pin "1") (pinfunction "RFIN_1") (pintype "unspecified"))
    )
    (net (code "61") (name "Net-(U9-BOOT)") (class "Default")
      (node (ref "C44") (pin "2") (pinfunction "2_2") (pintype "input"))
      (node (ref "U9") (pin "1") (pinfunction "BOOT_1") (pintype "input"))
    )
    (net (code "62") (name "Net-(U9-CMP)") (class "Default")
      (node (ref "C41") (pin "2") (pinfunction "2_2") (pintype "input"))
      (node (ref "R28") (pin "1") (pinfunction "1_1") (pintype "input"))
      (node (ref "U9") (pin "6") (pinfunction "CMP_6") (pintype "input"))
    )
    (net (code "63") (name "Net-(U9-FB)") (class "Default")
      (node (ref "R25") (pin "2") (pinfunction "2_2") (pintype "input"))
      (node (ref "R26") (pin "1") (pinfunction "1_1") (pintype "input"))
      (node (ref "U9") (pin "5") (pinfunction "FB_5") (pintype "input"))
    )
    (net (code "64") (name "Net-(U9-RT)") (class "Default")
      (node (ref "R27") (pin "1") (pinfunction "1_1") (pintype "input"))
      (node (ref "U9") (pin "4") (pinfunction "RT_4") (pintype "input"))
    )
    (net (code "65") (name "Net-(U11-BOOT0)") (class "Default")
      (node (ref "R39") (pin "2") (pinfunction "2_2") (pintype "input"))
      (node (ref "U11") (pin "60") (pinfunction "BOOT0_60") (pintype "unspecified"))
    )
    (net (code "66") (name "Net-(U11-NRST)") (class "Default")
      (node (ref "C55") (pin "1") (pinfunction "1_1") (pintype "input"))
      (node (ref "R40") (pin "1") (pinfunction "1_1") (pintype "input"))
      (node (ref "U11") (pin "7") (pinfunction "NRST_7") (pintype "unspecified"))
    )
    (net (code "67") (name "Net-(U11-PA13)") (class "Default")
      (node (ref "R45") (pin "2") (pinfunction "2_2") (pintype "input"))
      (node (ref "U11") (pin "46") (pinfunction "PA13_46") (pintype "unspecified"))
    )
    (net (code "68") (name "Net-(U11-PA14)") (class "Default")
      (node (ref "R43") (pin "2") (pinfunction "2_2") (pintype "input"))
      (node (ref "U11") (pin "49") (pinfunction "PA14_49") (pintype "unspecified"))
    )
    (net (code "69") (name "Net-(U11-VDDA)") (class "Default")
      (node (ref "R42") (pin "1") (pinfunction "1_1") (pintype "input"))
      (node (ref "U11") (pin "13") (pinfunction "VDDA_13") (pintype "unspecified"))
    )
    (net (code "70") (name "Net-(U12A-NONINVERTING_INPUT)") (class "Default")
      (node (ref "C8") (pin "2") (pinfunction "2_2") (pintype "input"))
      (node (ref "R2") (pin "2") (pinfunction "2_2") (pintype "input"))
      (node (ref "RT1") (pin "2") (pinfunction "2_2") (pintype "input"))
      (node (ref "U12") (pin "3") (pinfunction "NONINVERTING_INPUT_3") (pintype "unspecified"))
    )
    (net (code "71") (name "Net-(U12B-NONINVERTING_INPUT)") (class "Default")
      (node (ref "C14") (pin "2") (pinfunction "2_2") (pintype "input"))
      (node (ref "R4") (pin "2") (pinfunction "2_2") (pintype "input"))
      (node (ref "RT2") (pin "2") (pinfunction "2_2") (pintype "input"))
      (node (ref "U12") (pin "5") (pinfunction "NONINVERTING_INPUT_5") (pintype "unspecified"))
    )
    (net (code "72") (name "Net-(U13A-NONINVERTING_INPUT)") (class "Default")
      (node (ref "C6") (pin "2") (pinfunction "2_2") (pintype "input"))
      (node (ref "R1") (pin "2") (pinfunction "2_2") (pintype "input"))
      (node (ref "RT4") (pin "2") (pinfunction "2_2") (pintype "input"))
      (node (ref "U13") (pin "3") (pinfunction "NONINVERTING_INPUT_3") (pintype "unspecified"))
    )
    (net (code "73") (name "Net-(U13B-NONINVERTING_INPUT)") (class "Default")
      (node (ref "C13") (pin "2") (pinfunction "2_2") (pintype "input"))
      (node (ref "R3") (pin "2") (pinfunction "2_2") (pintype "input"))
      (node (ref "RT3") (pin "2") (pinfunction "2_2") (pintype "input"))
      (node (ref "U13") (pin "5") (pinfunction "NONINVERTING_INPUT_5") (pintype "unspecified"))
    )
    (net (code "74") (name "Net-(U14A-INVERTING_INPUT)") (class "Default")
      (node (ref "PR1") (pin "2") (pinfunction "2_2") (pintype "input"))
      (node (ref "U14") (pin "2") (pinfunction "INVERTING_INPUT_2") (pintype "unspecified"))
    )
    (net (code "75") (name "Net-(U14A-NONINVERTING_INPUT)") (class "Default")
      (node (ref "R33") (pin "1") (pinfunction "1_1") (pintype "input"))
      (node (ref "R34") (pin "1") (pinfunction "1_1") (pintype "input"))
      (node (ref "U14") (pin "3") (pinfunction "NONINVERTING_INPUT_3") (pintype "unspecified"))
    )
    (net (code "76") (name "Net-(USB1-CC1)") (class "Default")
      (node (ref "R30") (pin "1") (pinfunction "1_1") (pintype "input"))
      (node (ref "USB1") (pin "4") (pinfunction "CC1_4") (pintype "unspecified"))
    )
    (net (code "77") (name "Net-(USB1-CC2)") (class "Default")
      (node (ref "R29") (pin "1") (pinfunction "1_1") (pintype "input"))
      (node (ref "USB1") (pin "10") (pinfunction "CC2_10") (pintype "unspecified"))
    )
    (net (code "78") (name "OSC_IN") (class "Default")
      (node (ref "C57") (pin "2") (pinfunction "2_2") (pintype "input"))
      (node (ref "R44") (pin "1") (pinfunction "1_1") (pintype "input"))
      (node (ref "U11") (pin "5") (pinfunction "PD0-OSC_IN_5") (pintype "unspecified"))
      (node (ref "X1") (pin "2") (pinfunction "OSC2_2") (pintype "input"))
    )
    (net (code "79") (name "OSC_OUT") (class "Default")
      (node (ref "C58") (pin "2") (pinfunction "2_2") (pintype "input"))
      (node (ref "R44") (pin "2") (pinfunction "2_2") (pintype "input"))
      (node (ref "U11") (pin "6") (pinfunction "PD1-OSC_OUT_6") (pintype "unspecified"))
      (node (ref "X1") (pin "1") (pinfunction "OSC1_1") (pintype "input"))
    )
    (net (code "80") (name "RF_CE") (class "Default")
      (node (ref "CN6") (pin "2") (pinfunction "2_2") (pintype "unspecified"))
      (node (ref "R14") (pin "1") (pinfunction "1_1") (pintype "input"))
      (node (ref "U11") (pin "37") (pinfunction "PC6_37") (pintype "unspecified"))
    )
    (net (code "81") (name "RF_CS") (class "Default")
      (node (ref "CN6") (pin "3") (pinfunction "3_3") (pintype "unspecified"))
      (node (ref "R15") (pin "1") (pinfunction "1_1") (pintype "input"))
      (node (ref "U11") (pin "33") (pinfunction "PB12_33") (pintype "unspecified"))
    )
    (net (code "82") (name "RF_IRQ") (class "Default")
      (node (ref "CN6") (pin "7") (pinfunction "7_7") (pintype "unspecified"))
      (node (ref "R16") (pin "1") (pinfunction "1_1") (pintype "input"))
      (node (ref "U11") (pin "38") (pinfunction "PC7_38") (pintype "unspecified"))
    )
    (net (code "83") (name "RF_MISO") (class "Default")
      (node (ref "CN6") (pin "6") (pinfunction "6_6") (pintype "unspecified"))
      (node (ref "U11") (pin "35") (pinfunction "PB14_35") (pintype "unspecified"))
      (node (ref "U6") (pin "2") (pinfunction "DO（IO1）_2") (pintype "unspecified"))
    )
    (net (code "84") (name "RF_MOSI") (class "Default")
      (node (ref "CN6") (pin "5") (pinfunction "5_5") (pintype "unspecified"))
      (node (ref "U11") (pin "36") (pinfunction "PB15_36") (pintype "unspecified"))
      (node (ref "U6") (pin "5") (pinfunction "DI（IO0）_5") (pintype "unspecified"))
    )
    (net (code "85") (name "RF_SCLK") (class "Default")
      (node (ref "CN6") (pin "4") (pinfunction "4_4") (pintype "unspecified"))
      (node (ref "U11") (pin "34") (pinfunction "PB13_34") (pintype "unspecified"))
      (node (ref "U6") (pin "6") (pinfunction "CLK_6") (pintype "unspecified"))
    )
    (net (code "86") (name "S_ADJ") (class "Default")
      (node (ref "C56") (pin "2") (pinfunction "2_2") (pintype "input"))
      (node (ref "R41") (pin "2") (pinfunction "2_2") (pintype "input"))
      (node (ref "U11") (pin "25") (pinfunction "PC5_25") (pintype "unspecified"))
    )
    (net (code "87") (name "S_INT") (class "Default")
      (node (ref "U11") (pin "57") (pinfunction "PB5_57") (pintype "unspecified"))
      (node (ref "U5") (pin "12") (pinfunction "INT_12") (pintype "unspecified"))
    )
    (net (code "88") (name "S_SCL") (class "Default")
      (node (ref "R17") (pin "1") (pinfunction "1_1") (pintype "input"))
      (node (ref "U11") (pin "58") (pinfunction "PB6_58") (pintype "unspecified"))
      (node (ref "U5") (pin "24") (pinfunction "SDA_24") (pintype "unspecified"))
    )
    (net (code "89") (name "S_SDA") (class "Default")
      (node (ref "R18") (pin "1") (pinfunction "1_1") (pintype "input"))
      (node (ref "U11") (pin "59") (pinfunction "PB7_59") (pintype "unspecified"))
      (node (ref "U5") (pin "23") (pinfunction "SCL_23") (pintype "unspecified"))
    )
    (net (code "90") (name "TIMA_CH1") (class "Default")
      (node (ref "U11") (pin "14") (pinfunction "PA0-WKUP_14") (pintype "unspecified"))
      (node (ref "U2") (pin "3") (pinfunction "IN1_3") (pintype "unspecified"))
    )
    (net (code "91") (name "TIMA_CH2") (class "Default")
      (node (ref "U11") (pin "15") (pinfunction "PA1_15") (pintype "unspecified"))
      (node (ref "U2") (pin "2") (pinfunction "IN2_2") (pintype "unspecified"))
    )
    (net (code "92") (name "TIMB_CH1") (class "Default")
      (node (ref "U11") (pin "16") (pinfunction "PA2_16") (pintype "unspecified"))
      (node (ref "U4") (pin "3") (pinfunction "IN1_3") (pintype "unspecified"))
    )
    (net (code "93") (name "TIMB_CH2") (class "Default")
      (node (ref "U11") (pin "17") (pinfunction "PA3_17") (pintype "unspecified"))
      (node (ref "U4") (pin "2") (pinfunction "IN2_2") (pintype "unspecified"))
    )
    (net (code "94") (name "TIMC_CH1") (class "Default")
      (node (ref "U11") (pin "20") (pinfunction "PA4_20") (pintype "unspecified"))
      (node (ref "U3") (pin "3") (pinfunction "IN1_3") (pintype "unspecified"))
    )
    (net (code "95") (name "TIMC_CH2") (class "Default")
      (node (ref "U11") (pin "21") (pinfunction "PA5_21") (pintype "unspecified"))
      (node (ref "U3") (pin "2") (pinfunction "IN2_2") (pintype "unspecified"))
    )
    (net (code "96") (name "TIMD_CH1") (class "Default")
      (node (ref "U1") (pin "3") (pinfunction "IN1_3") (pintype "unspecified"))
      (node (ref "U11") (pin "22") (pinfunction "PA6_22") (pintype "unspecified"))
    )
    (net (code "97") (name "TIMD_CH2") (class "Default")
      (node (ref "U1") (pin "2") (pinfunction "IN2_2") (pintype "unspecified"))
      (node (ref "U11") (pin "23") (pinfunction "PA7_23") (pintype "unspecified"))
    )
    (net (code "98") (name "USB_DN") (class "Default")
      (node (ref "U11") (pin "44") (pinfunction "PA11_44") (pintype "unspecified"))
      (node (ref "USB1") (pin "5") (pinfunction "DN2_5") (pintype "unspecified"))
      (node (ref "USB1") (pin "7") (pinfunction "DN1_7") (pintype "unspecified"))
    )
    (net (code "99") (name "USB_DP") (class "Default")
      (node (ref "U11") (pin "45") (pinfunction "PA12_45") (pintype "unspecified"))
      (node (ref "USB1") (pin "6") (pinfunction "DP1_6") (pintype "unspecified"))
      (node (ref "USB1") (pin "8") (pinfunction "DP2_8") (pintype "unspecified"))
    )
    (net (code "100") (name "USR_LED1") (class "Default")
      (node (ref "LED2") (pin "1") (pinfunction "C_1") (pintype "input"))
      (node (ref "U11") (pin "53") (pinfunction "PC12_53") (pintype "unspecified"))
    )
    (net (code "101") (name "USR_LED2") (class "Default")
      (node (ref "LED3") (pin "1") (pinfunction "C_1") (pintype "input"))
      (node (ref "U11") (pin "2") (pinfunction "PC13-TAMPER-RTC_2") (pintype "unspecified"))
    )
    (net (code "102") (name "USR_LED3") (class "Default")
      (node (ref "LED4") (pin "1") (pinfunction "C_1") (pintype "input"))
      (node (ref "U11") (pin "3") (pinfunction "PC14-OSC32_IN_3") (pintype "unspecified"))
    )
    (net (code "103") (name "USR_LED4") (class "Default")
      (node (ref "LED5") (pin "1") (pinfunction "C_1") (pintype "input"))
      (node (ref "U11") (pin "4") (pinfunction "PC15-OSC32_OUT_4") (pintype "unspecified"))
    )
    (net (code "104") (name "VBAT") (class "Default")
      (node (ref "C16") (pin "1") (pinfunction "1_1") (pintype "input"))
      (node (ref "C17") (pin "2") (pinfunction "2_2") (pintype "input"))
      (node (ref "C19") (pin "1") (pinfunction "1_1") (pintype "input"))
      (node (ref "C20") (pin "2") (pinfunction "2_2") (pintype "input"))
      (node (ref "C22") (pin "1") (pinfunction "1_1") (pintype "input"))
      (node (ref "C23") (pin "2") (pinfunction "2_2") (pintype "input"))
      (node (ref "C25") (pin "1") (pinfunction "1_1") (pintype "input"))
      (node (ref "C26") (pin "2") (pinfunction "2_2") (pintype "input"))
      (node (ref "CN7") (pin "1") (pinfunction "1_1") (pintype "unspecified"))
      (node (ref "D5") (pin "2") (pinfunction "A_2") (pintype "unspecified"))
      (node (ref "R31") (pin "1") (pinfunction "1_1") (pintype "input"))
      (node (ref "R33") (pin "2") (pinfunction "2_2") (pintype "input"))
      (node (ref "U1") (pin "5") (pinfunction "VM_5") (pintype "unspecified"))
      (node (ref "U2") (pin "5") (pinfunction "VM_5") (pintype "unspecified"))
      (node (ref "U3") (pin "5") (pinfunction "VM_5") (pintype "unspecified"))
      (node (ref "U4") (pin "5") (pinfunction "VM_5") (pintype "unspecified"))
    )
    (net (code "105") (name "VBUS") (class "Default")
      (node (ref "D7") (pin "2") (pinfunction "A_2") (pintype "unspecified"))
      (node (ref "USB1") (pin "11") (pinfunction "VBUS_11") (pintype "unspecified"))
      (node (ref "USB1") (pin "2") (pinfunction "VBUS_2") (pintype "unspecified"))
    )
    (net (code "106") (name "VDD") (class "Default")
      (node (ref "C1") (pin "2") (pinfunction "2_2") (pintype "input"))
      (node (ref "C15") (pin "2") (pinfunction "2_2") (pintype "input"))
      (node (ref "C18") (pin "2") (pinfunction "2_2") (pintype "input"))
      (node (ref "C2") (pin "2") (pinfunction "2_2") (pintype "input"))
      (node (ref "C21") (pin "2") (pinfunction "2_2") (pintype "input"))
      (node (ref "C24") (pin "2") (pinfunction "2_2") (pintype "input"))
      (node (ref "C28") (pin "1") (pinfunction "1_1") (pintype "input"))
      (node (ref "C29") (pin "1") (pinfunction "1_1") (pintype "input"))
      (node (ref "C30") (pin "1") (pinfunction "1_1") (pintype "input"))
      (node (ref "C33") (pin "2") (pinfunction "2_2") (pintype "input"))
      (node (ref "C34") (pin "1") (pinfunction "1_1") (pintype "input"))
      (node (ref "C36") (pin "1") (pinfunction "1_1") (pintype "input"))
      (node (ref "C38") (pin "2") (pinfunction "2_2") (pintype "input"))
      (node (ref "C39") (pin "2") (pinfunction "2_2") (pintype "input"))
      (node (ref "C47") (pin "1") (pinfunction "1_1") (pintype "input"))
      (node (ref "C49") (pin "1") (pinfunction "1_1") (pintype "input"))
      (node (ref "C51") (pin "1") (pinfunction "1_1") (pintype "input"))
      (node (ref "C54") (pin "1") (pinfunction "1_1") (pintype "input"))
      (node (ref "C59") (pin "1") (pinfunction "1_1") (pintype "input"))
      (node (ref "C60") (pin "1") (pinfunction "1_1") (pintype "input"))
      (node (ref "C61") (pin "1") (pinfunction "1_1") (pintype "input"))
      (node (ref "C62") (pin "1") (pinfunction "1_1") (pintype "input"))
      (node (ref "CN6") (pin "1") (pinfunction "1_1") (pintype "unspecified"))
      (node (ref "H1") (pin "1") (pinfunction "1_1") (pintype "unspecified"))
      (node (ref "H2") (pin "2") (pinfunction "2_2") (pintype "unspecified"))
      (node (ref "LED1") (pin "2") (pinfunction "A_2") (pintype "input"))
      (node (ref "PR1") (pin "1") (pinfunction "1_1") (pintype "input"))
      (node (ref "PR2") (pin "3") (pinfunction "3_3") (pintype "input"))
      (node (ref "R14") (pin "2") (pinfunction "2_2") (pintype "input"))
      (node (ref "R15") (pin "2") (pinfunction "2_2") (pintype "input"))
      (node (ref "R16") (pin "2") (pinfunction "2_2") (pintype "input"))
      (node (ref "R17") (pin "2") (pinfunction "2_2") (pintype "input"))
      (node (ref "R18") (pin "2") (pinfunction "2_2") (pintype "input"))
      (node (ref "R20") (pin "2") (pinfunction "2_2") (pintype "input"))
      (node (ref "R35") (pin "2") (pinfunction "2_2") (pintype "input"))
      (node (ref "R36") (pin "2") (pinfunction "2_2") (pintype "input"))
      (node (ref "R37") (pin "2") (pinfunction "2_2") (pintype "input"))
      (node (ref "R38") (pin "2") (pinfunction "2_2") (pintype "input"))
      (node (ref "R40") (pin "2") (pinfunction "2_2") (pintype "input"))
      (node (ref "R42") (pin "2") (pinfunction "2_2") (pintype "input"))
      (node (ref "RT1") (pin "1") (pinfunction "1_1") (pintype "input"))
      (node (ref "RT2") (pin "1") (pinfunction "1_1") (pintype "input"))
      (node (ref "RT3") (pin "1") (pinfunction "1_1") (pintype "input"))
      (node (ref "RT4") (pin "1") (pinfunction "1_1") (pintype "input"))
      (node (ref "U1") (pin "4") (pinfunction "VREF_4") (pintype "unspecified"))
      (node (ref "U10") (pin "5") (pinfunction "VOUT_5") (pintype "unspecified"))
      (node (ref "U11") (pin "1") (pinfunction "VBAT_1") (pintype "unspecified"))
      (node (ref "U11") (pin "19") (pinfunction "VDD_4_19") (pintype "unspecified"))
      (node (ref "U11") (pin "32") (pinfunction "VDD_1_32") (pintype "unspecified"))
      (node (ref "U11") (pin "48") (pinfunction "VDD_2_48") (pintype "unspecified"))
      (node (ref "U11") (pin "64") (pinfunction "VDD_3_64") (pintype "unspecified"))
      (node (ref "U12") (pin "8") (pinfunction "+V_8") (pintype "unspecified"))
      (node (ref "U13") (pin "8") (pinfunction "+V_8") (pintype "unspecified"))
      (node (ref "U14") (pin "8") (pinfunction "+V_8") (pintype "unspecified"))
      (node (ref "U2") (pin "4") (pinfunction "VREF_4") (pintype "unspecified"))
      (node (ref "U3") (pin "4") (pinfunction "VREF_4") (pintype "unspecified"))
      (node (ref "U4") (pin "4") (pinfunction "VREF_4") (pintype "unspecified"))
      (node (ref "U5") (pin "13") (pinfunction "VDD_13") (pintype "unspecified"))
      (node (ref "U5") (pin "8") (pinfunction "VLOGIC_8") (pintype "unspecified"))
      (node (ref "U6") (pin "3") (pinfunction "IO2_3") (pintype "unspecified"))
      (node (ref "U6") (pin "7") (pinfunction "IO3_7") (pintype "unspecified"))
      (node (ref "U6") (pin "8") (pinfunction "VCC_8") (pintype "unspecified"))
      (node (ref "U7") (pin "8") (pinfunction "VCC_8") (pintype "unspecified"))
      (node (ref "U8") (pin "5") (pinfunction "SHDN#_5") (pintype "unspecified"))
      (node (ref "U8") (pin "6") (pinfunction "VDD_6") (pintype "unspecified"))
    )
    (net (code "107") (name "unconnected-(U5-NC-Pad2)") (class "Default")
      (node (ref "U5") (pin "2") (pinfunction "NC_2") (pintype "unspecified+no_connect"))
    )
    (net (code "108") (name "unconnected-(U5-NC-Pad3)") (class "Default")
      (node (ref "U5") (pin "3") (pinfunction "NC_3") (pintype "unspecified+no_connect"))
    )
    (net (code "109") (name "unconnected-(U5-NC-Pad4)") (class "Default")
      (node (ref "U5") (pin "4") (pinfunction "NC_4") (pintype "unspecified+no_connect"))
    )
    (net (code "110") (name "unconnected-(U5-NC-Pad5)") (class "Default")
      (node (ref "U5") (pin "5") (pinfunction "NC_5") (pintype "unspecified+no_connect"))
    )
    (net (code "111") (name "unconnected-(U5-NC-Pad14)") (class "Default")
      (node (ref "U5") (pin "14") (pinfunction "NC_14") (pintype "unspecified+no_connect"))
    )
    (net (code "112") (name "unconnected-(U5-NC-Pad15)") (class "Default")
      (node (ref "U5") (pin "15") (pinfunction "NC_15") (pintype "unspecified+no_connect"))
    )
    (net (code "113") (name "unconnected-(U5-NC-Pad16)") (class "Default")
      (node (ref "U5") (pin "16") (pinfunction "NC_16") (pintype "unspecified+no_connect"))
    )
    (net (code "114") (name "unconnected-(U5-NC-Pad17)") (class "Default")
      (node (ref "U5") (pin "17") (pinfunction "NC_17") (pintype "unspecified+no_connect"))
    )
    (net (code "115") (name "unconnected-(U5-RESV-Pad19)") (class "Default")
      (node (ref "U5") (pin "19") (pinfunction "RESV_19") (pintype "unspecified+no_connect"))
    )
    (net (code "116") (name "unconnected-(U5-RESV-Pad21)") (class "Default")
      (node (ref "U5") (pin "21") (pinfunction "RESV_21") (pintype "unspecified+no_connect"))
    )
    (net (code "117") (name "unconnected-(U5-RESV-Pad22)") (class "Default")
      (node (ref "U5") (pin "22") (pinfunction "RESV_22") (pintype "unspecified+no_connect"))
    )
    (net (code "118") (name "unconnected-(U7-NC-Pad7)") (class "Default")
      (node (ref "U7") (pin "7") (pinfunction "NC_7") (pintype "unspecified+no_connect"))
    )
    (net (code "119") (name "unconnected-(U7-NC-Pad13)") (class "Default")
      (node (ref "U7") (pin "13") (pinfunction "NC_13") (pintype "unspecified+no_connect"))
    )
    (net (code "120") (name "unconnected-(U7-Reserved-Pad15)") (class "Default")
      (node (ref "U7") (pin "15") (pinfunction "Reserved_15") (pintype "unspecified+no_connect"))
    )
    (net (code "121") (name "unconnected-(U7-Reserved-Pad18)") (class "Default")
      (node (ref "U7") (pin "18") (pinfunction "Reserved_18") (pintype "unspecified+no_connect"))
    )
    (net (code "122") (name "unconnected-(U7-SCL-Pad17)") (class "Default")
      (node (ref "U7") (pin "17") (pinfunction "SCL_17") (pintype "unspecified+no_connect"))
    )
    (net (code "123") (name "unconnected-(U7-SDA-Pad16)") (class "Default")
      (node (ref "U7") (pin "16") (pinfunction "SDA_16") (pintype "unspecified+no_connect"))
    )
    (net (code "124") (name "unconnected-(U10-NC-Pad1)") (class "Default")
      (node (ref "U10") (pin "1") (pinfunction "NC_1") (pintype "unspecified+no_connect"))
    )
    (net (code "125") (name "unconnected-(U10-NC-Pad3)") (class "Default")
      (node (ref "U10") (pin "3") (pinfunction "NC_3") (pintype "unspecified+no_connect"))
    )
    (net (code "126") (name "unconnected-(U11-PB2-Pad28)") (class "Default")
      (node (ref "U11") (pin "28") (pinfunction "PB2_28") (pintype "unspecified+no_connect"))
    )
    (net (code "127") (name "unconnected-(U11-PB3-Pad55)") (class "Default")
      (node (ref "U11") (pin "55") (pinfunction "PB3_55") (pintype "unspecified+no_connect"))
    )
    (net (code "128") (name "unconnected-(U11-PB4-Pad56)") (class "Default")
      (node (ref "U11") (pin "56") (pinfunction "PB4_56") (pintype "unspecified+no_connect"))
    )
    (net (code "129") (name "unconnected-(U11-PB8-Pad61)") (class "Default")
      (node (ref "U11") (pin "61") (pinfunction "PB8_61") (pintype "unspecified+no_connect"))
    )
    (net (code "130") (name "unconnected-(U11-PB9-Pad62)") (class "Default")
      (node (ref "U11") (pin "62") (pinfunction "PB9_62") (pintype "unspecified+no_connect"))
    )
    (net (code "131") (name "unconnected-(U11-PC9-Pad40)") (class "Default")
      (node (ref "U11") (pin "40") (pinfunction "PC9_40") (pintype "unspecified+no_connect"))
    )
    (net (code "132") (name "unconnected-(U11-PC10-Pad51)") (class "Default")
      (node (ref "U11") (pin "51") (pinfunction "PC10_51") (pintype "unspecified+no_connect"))
    )
    (net (code "133") (name "unconnected-(U11-PC11-Pad52)") (class "Default")
      (node (ref "U11") (pin "52") (pinfunction "PC11_52") (pintype "unspecified+no_connect"))
    )
    (net (code "134") (name "unconnected-(U11-PD2-Pad54)") (class "Default")
      (node (ref "U11") (pin "54") (pinfunction "PD2_54") (pintype "unspecified+no_connect"))
    )
    (net (code "135") (name "unconnected-(USB1-SBU1-Pad9)") (class "Default")
      (node (ref "USB1") (pin "9") (pinfunction "SBU1_9") (pintype "unspecified+no_connect"))
    )
    (net (code "136") (name "unconnected-(USB1-SBU2-Pad3)") (class "Default")
      (node (ref "USB1") (pin "3") (pinfunction "SBU2_3") (pintype "unspecified+no_connect"))
    )
  )
)
